# in3watch.net
KiCad netlist of a schematic drawn in EAGLE
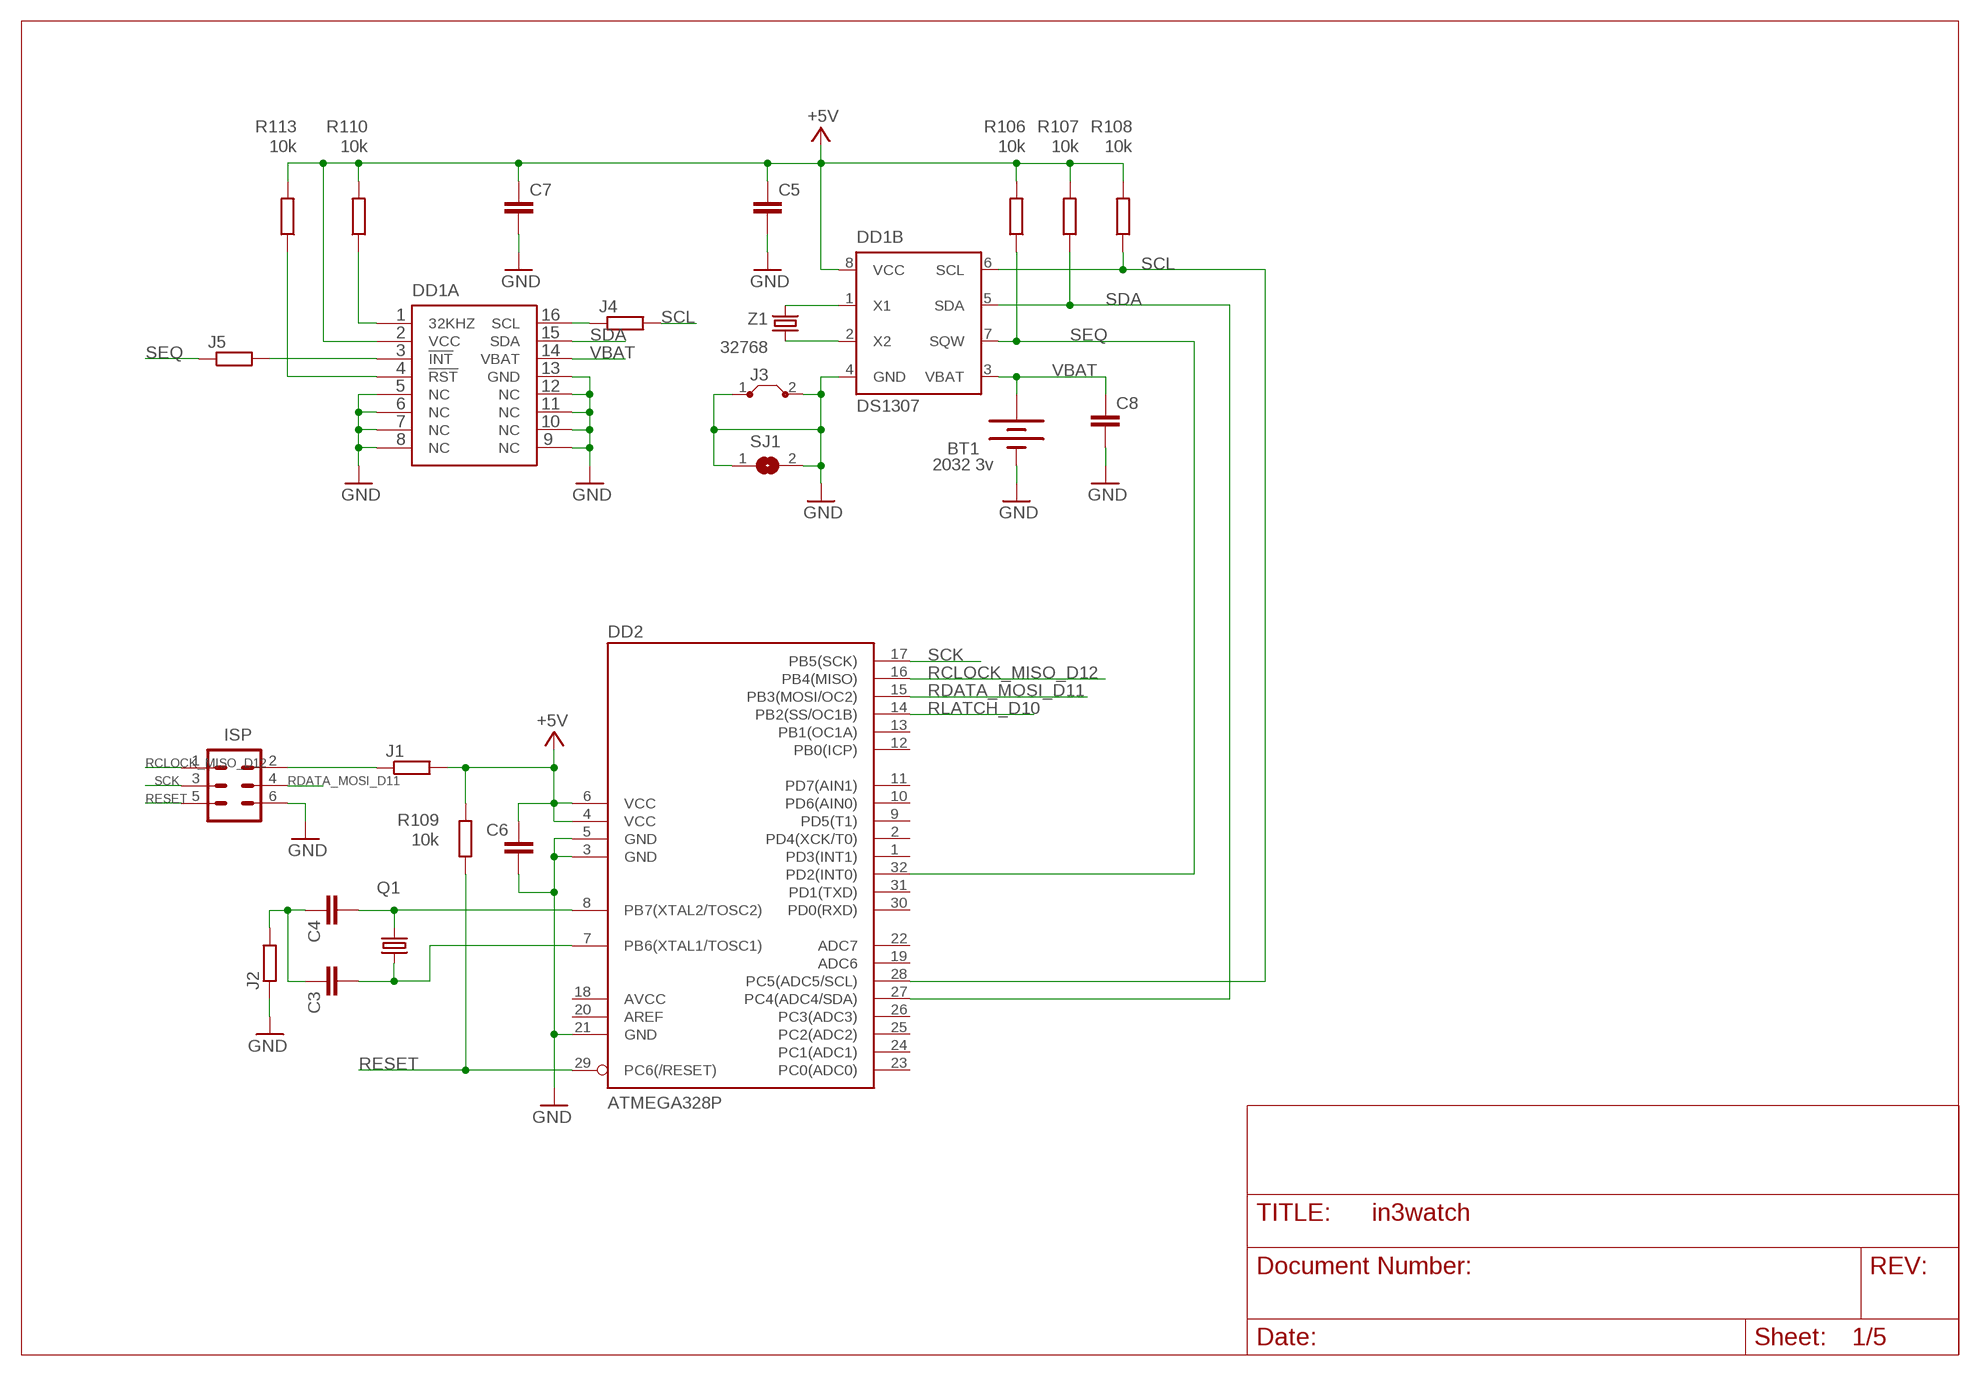
[diagram p0: schematic, sheet 1]
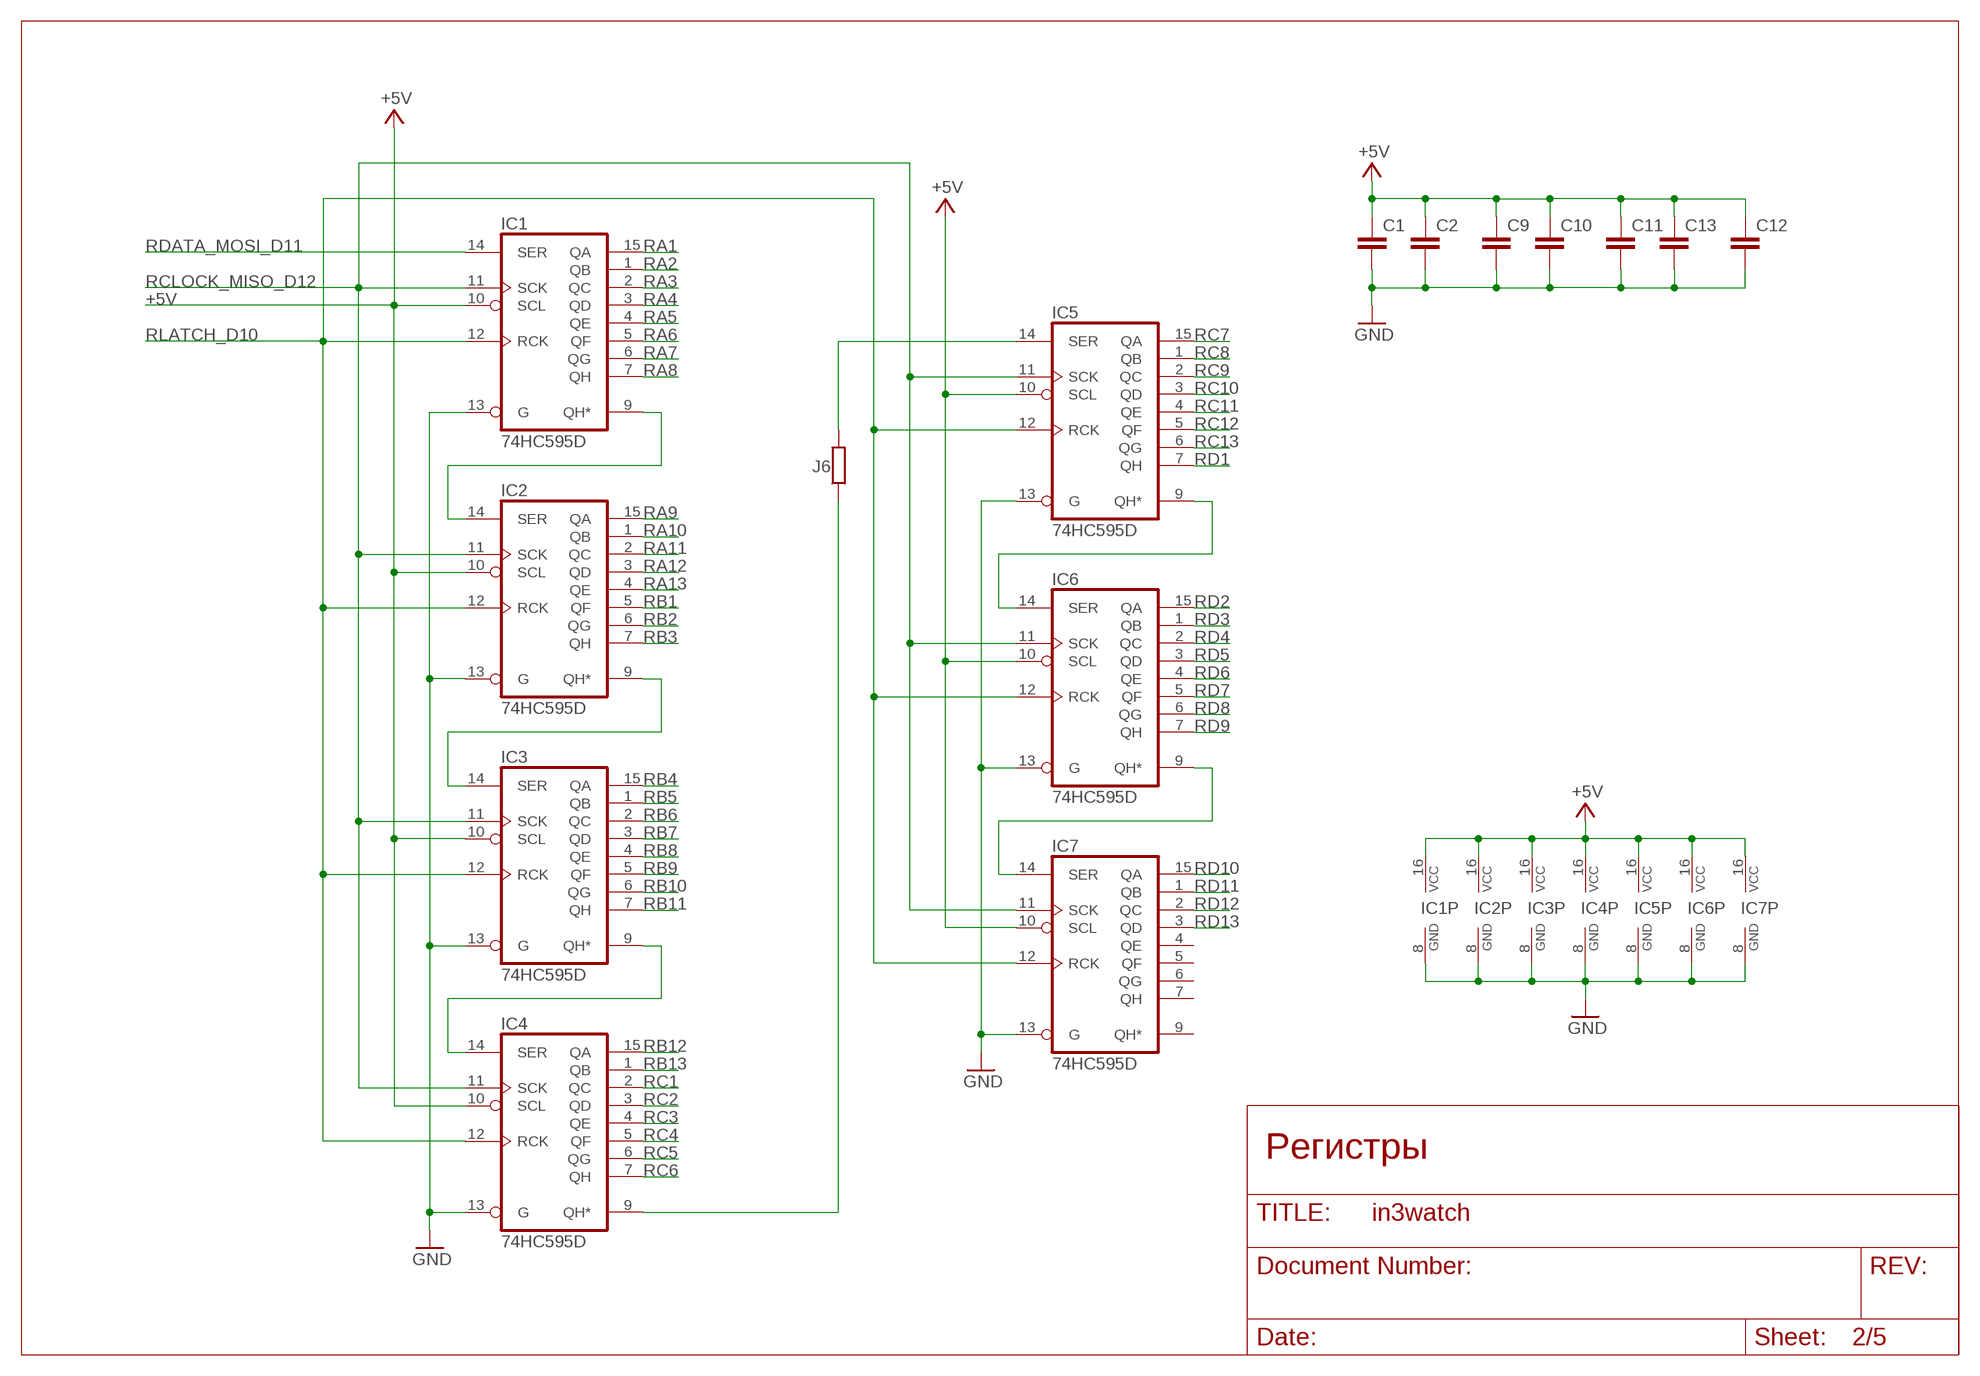
[diagram p1: schematic, sheet 2]
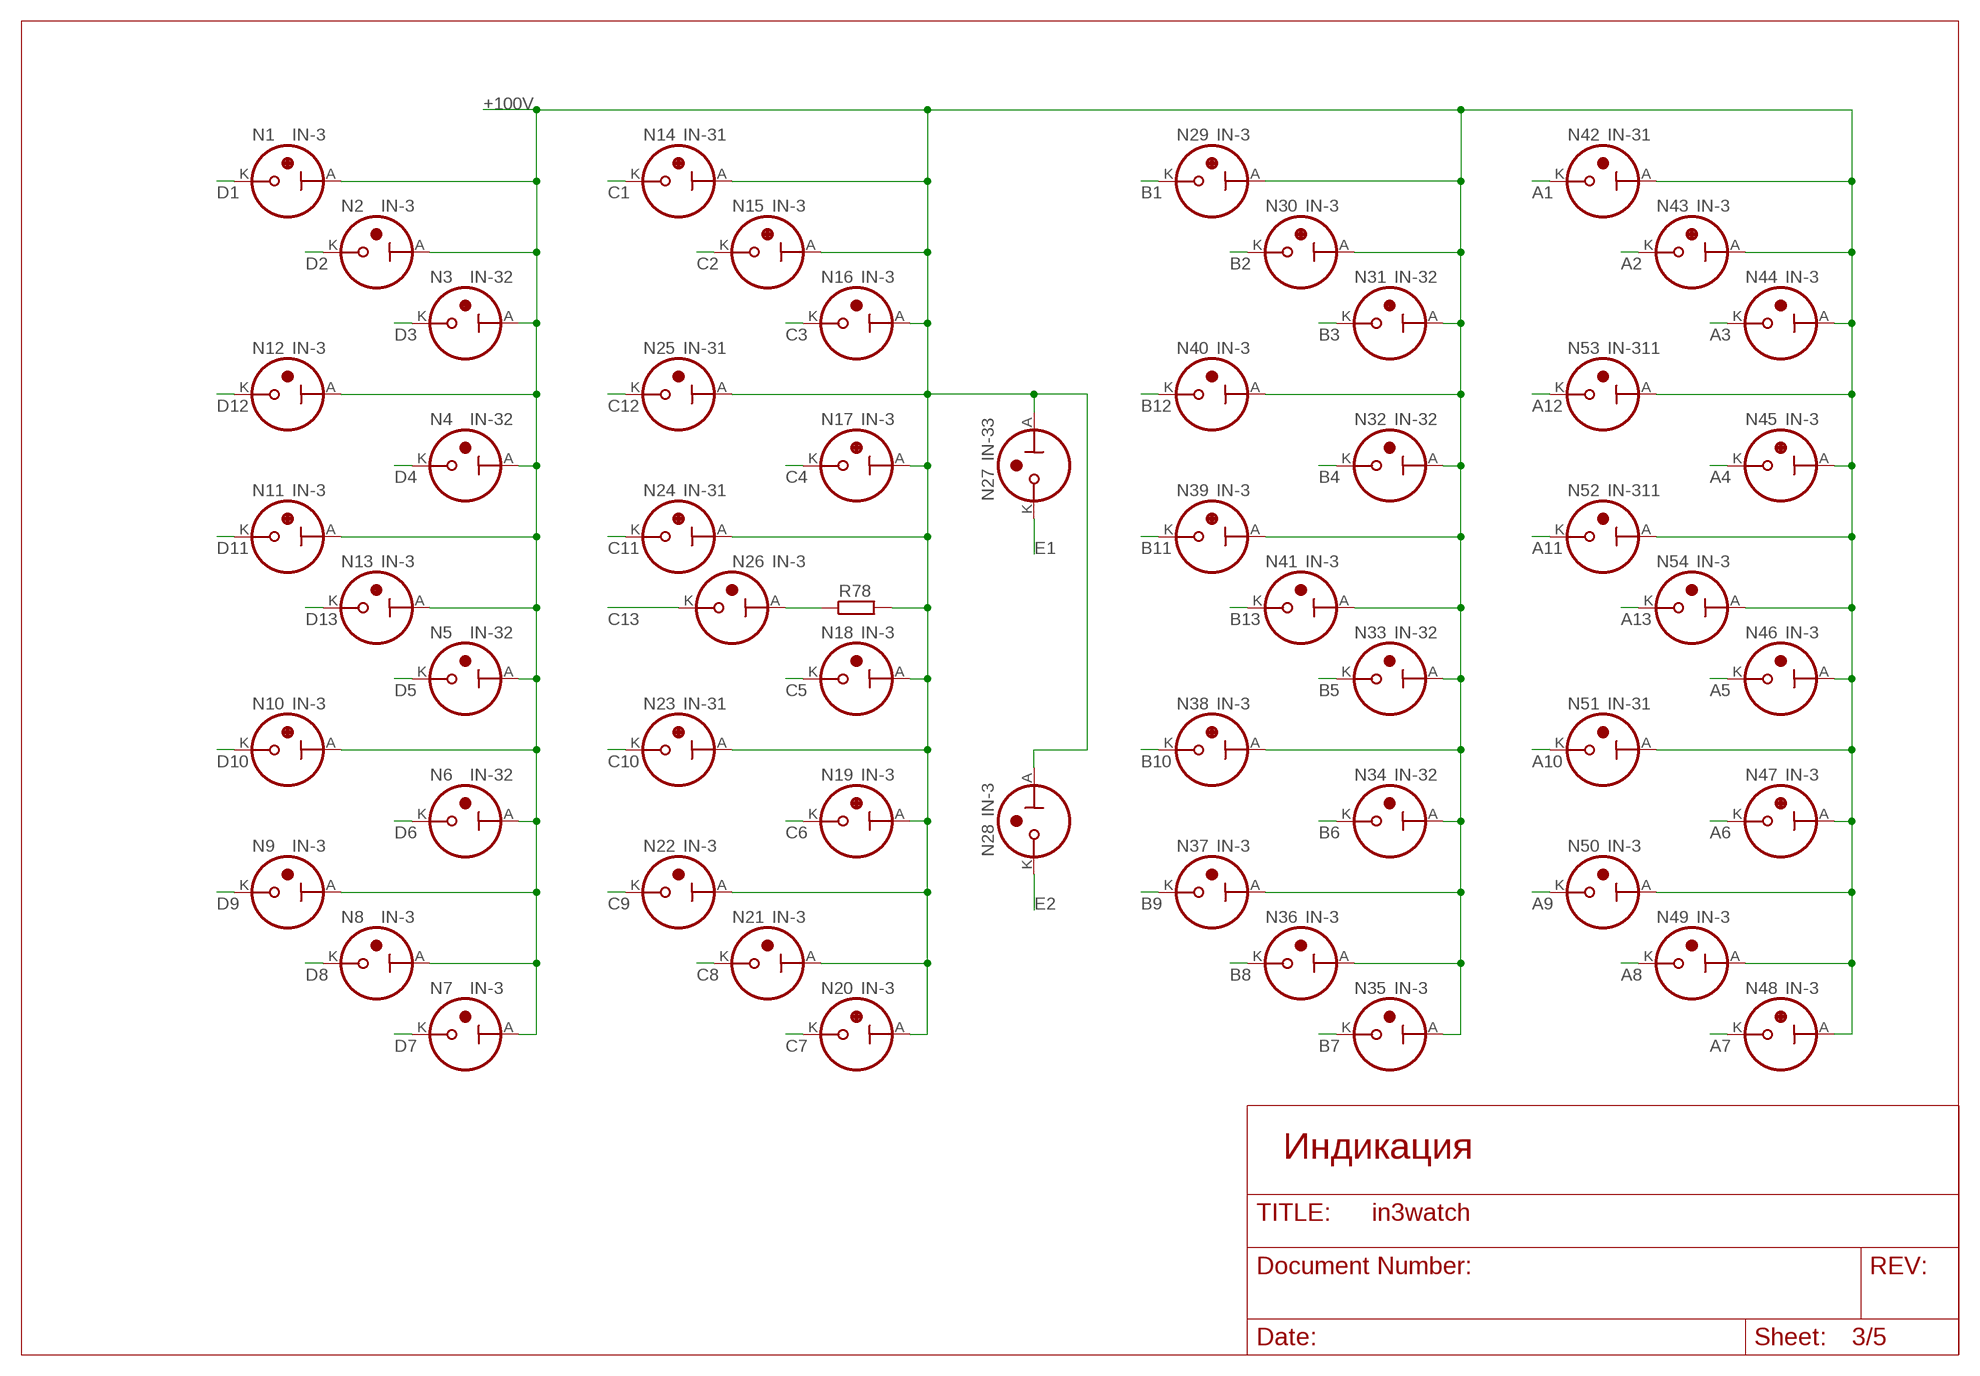
[diagram p2: schematic, sheet 3]
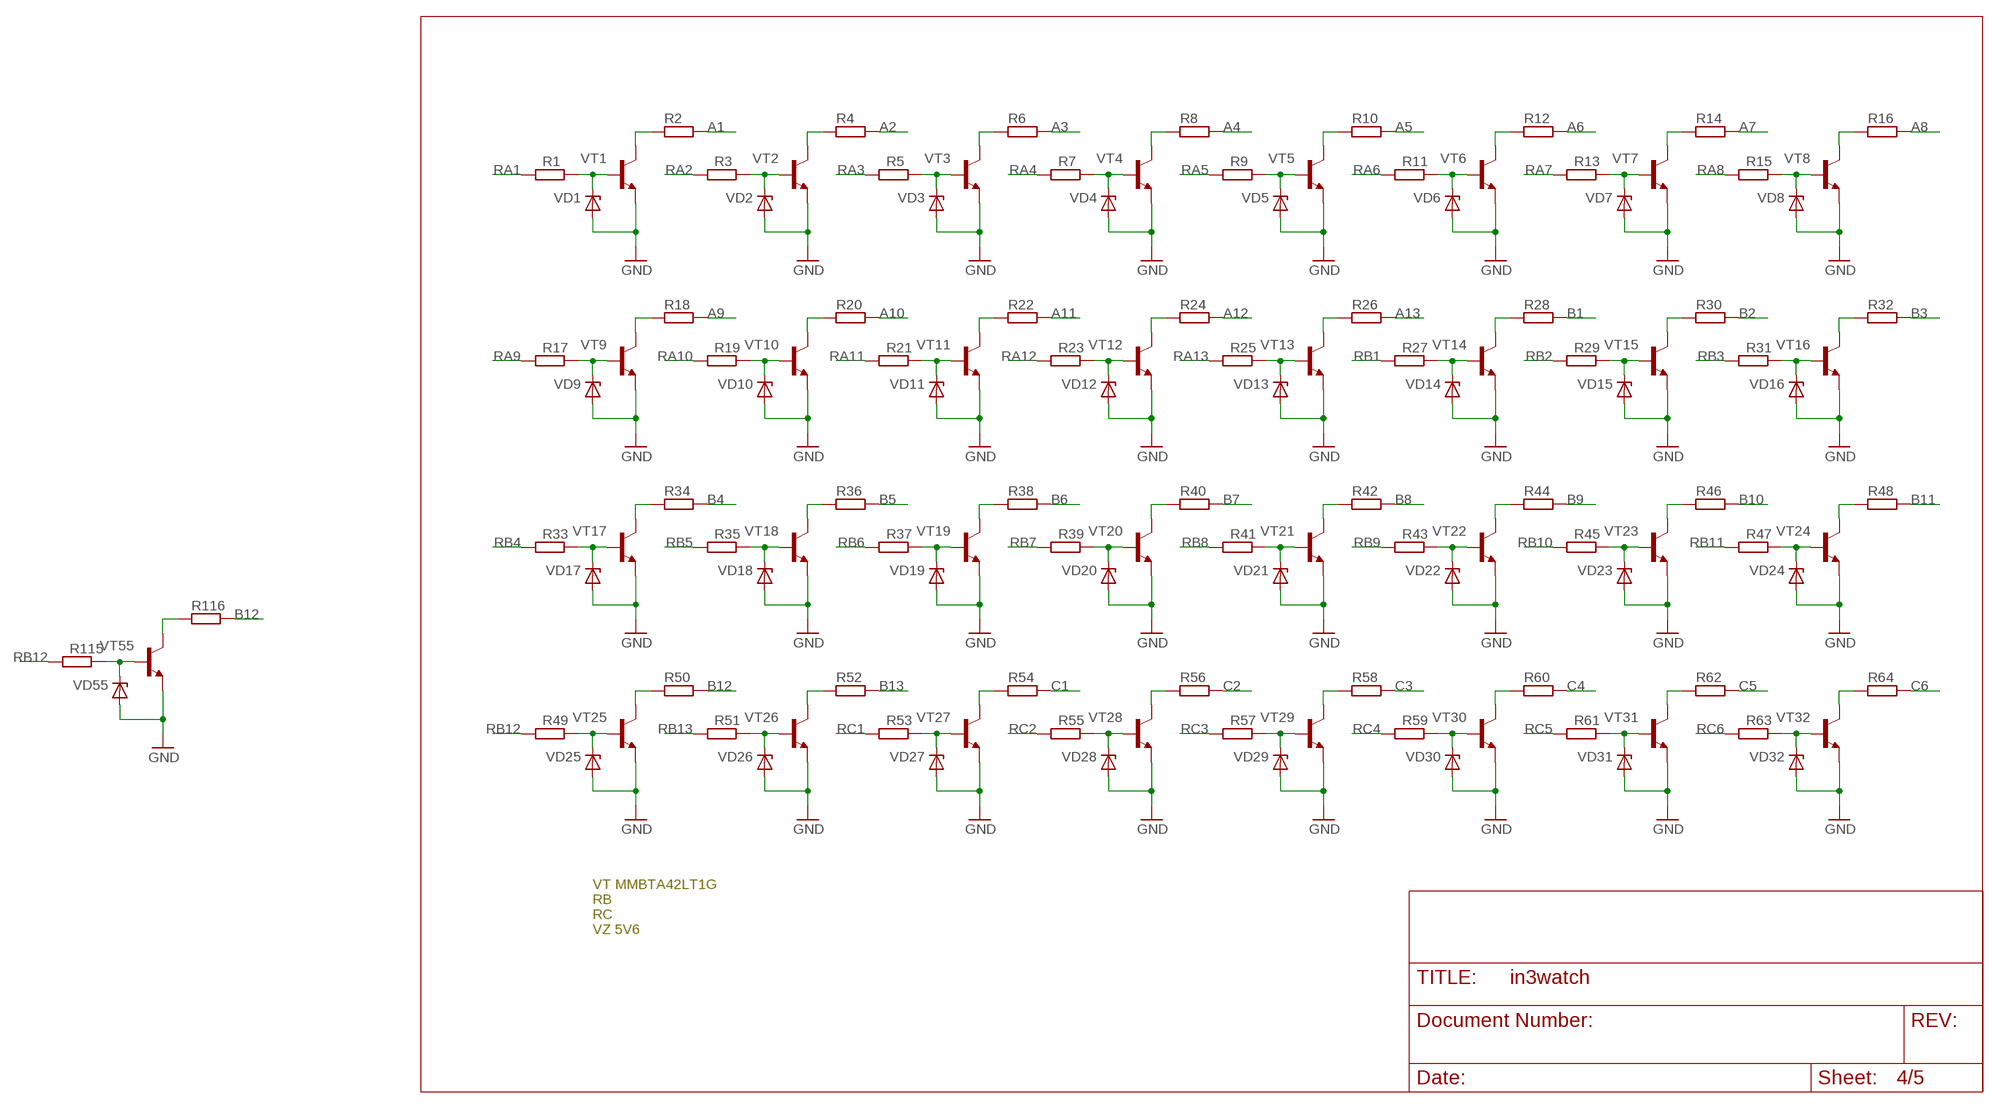
[diagram p3: schematic, sheet 4]
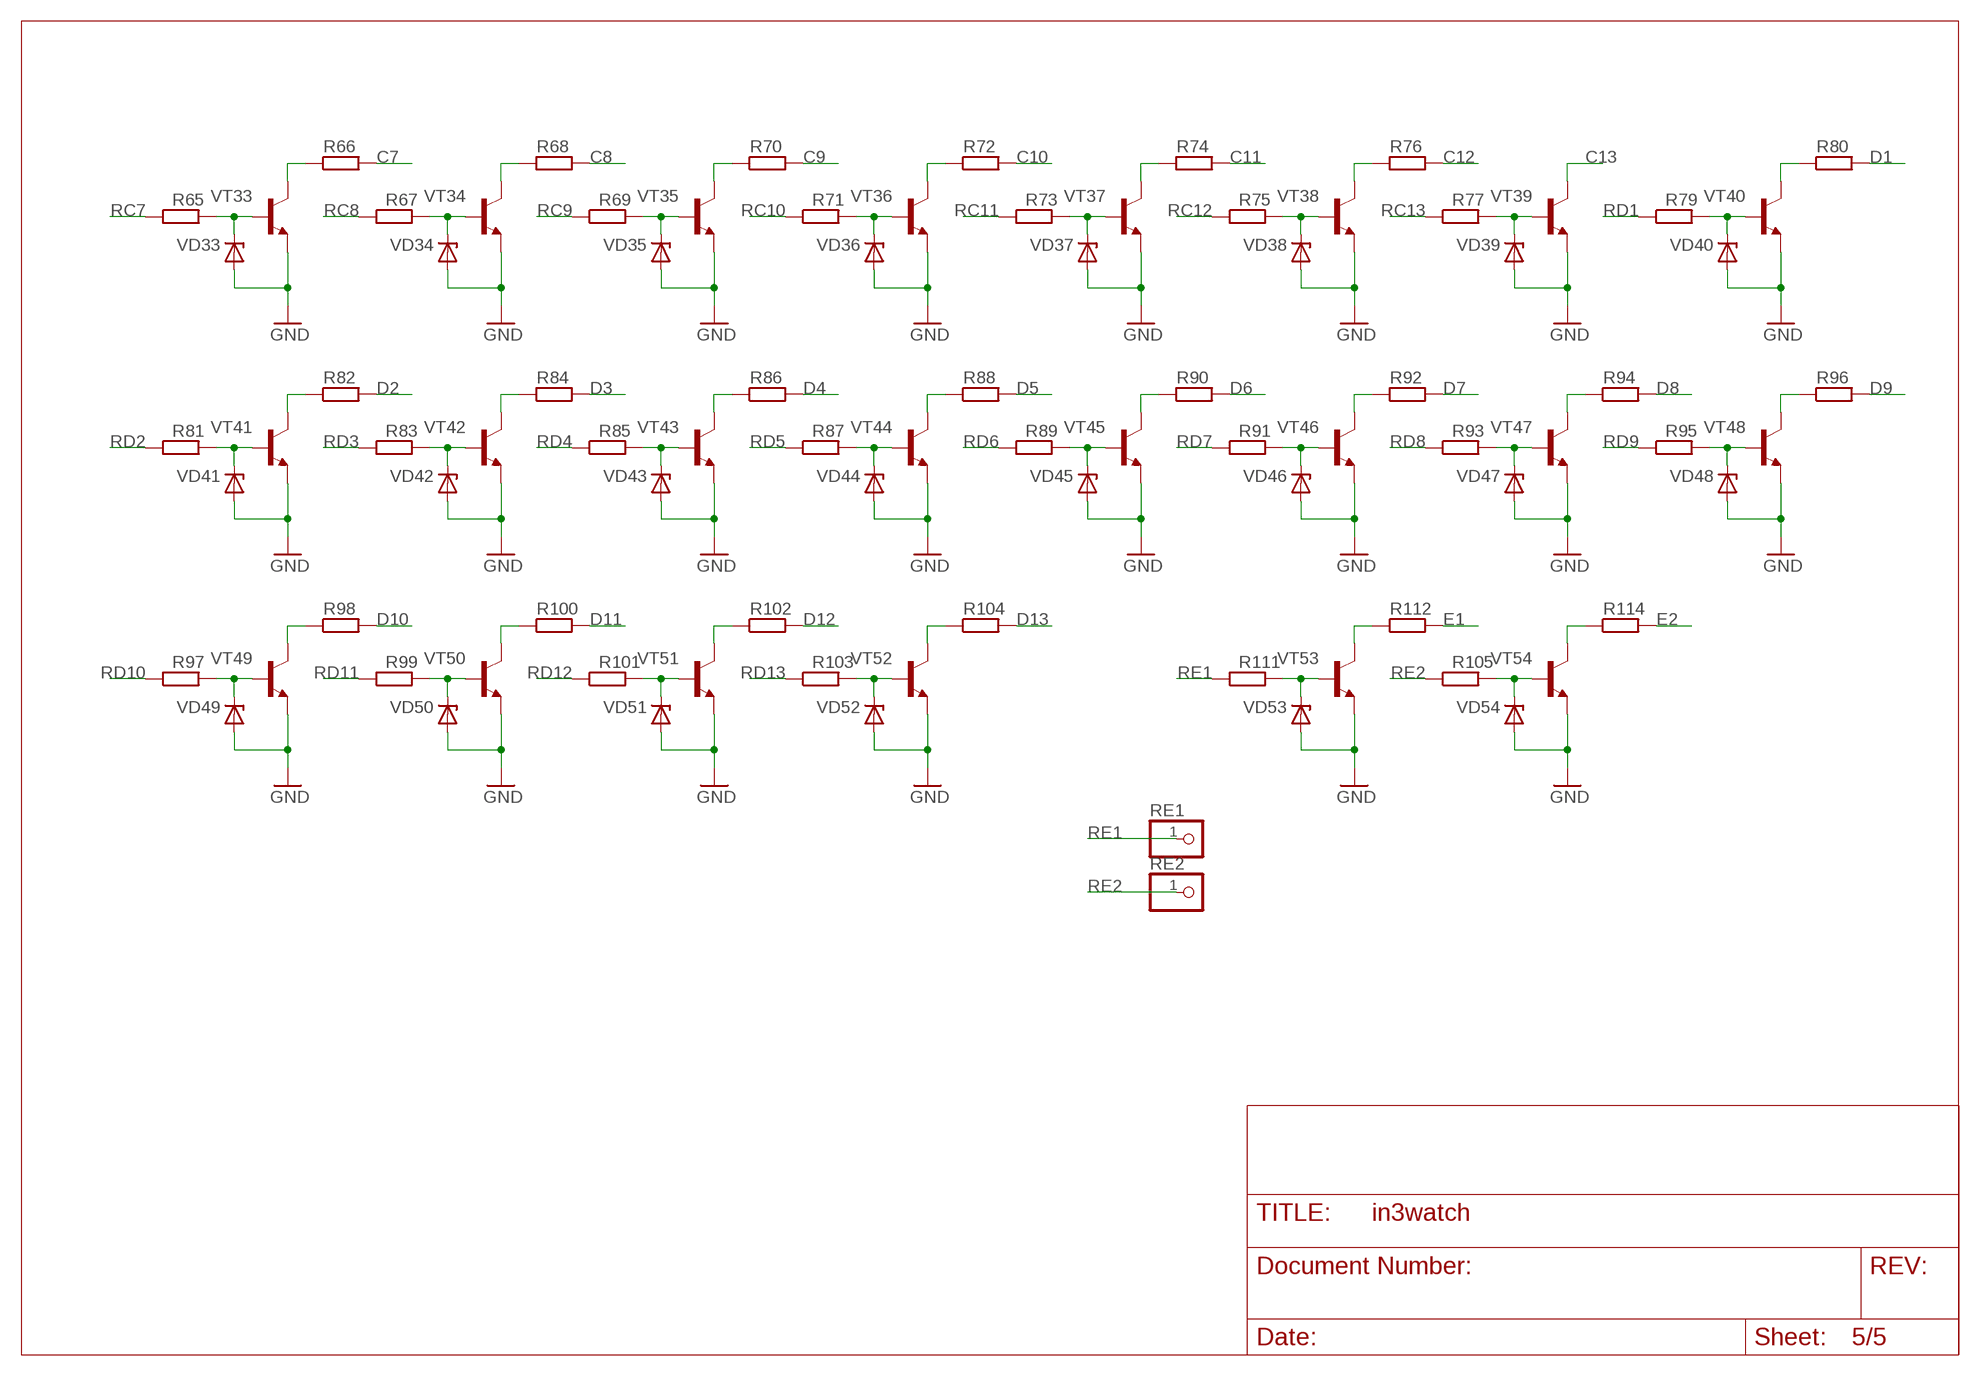
[diagram p4: schematic, sheet 5]

(export (version "E")
  (design (tool "Eeschema 10.0.6"))
  (components
    (comp (ref "N1")
      (value "IN-3")
      (footprint "eagle-import:IN-3")
      (libsource (lib "eagle-import") (part "IN-3"))
    )
    (comp (ref "N2")
      (value "IN-3")
      (footprint "eagle-import:IN-3")
      (libsource (lib "eagle-import") (part "IN-3"))
    )
    (comp (ref "N3")
      (value "IN-32")
      (footprint "eagle-import:IN-3-2")
      (libsource (lib "eagle-import") (part "IN-32"))
    )
    (comp (ref "N4")
      (value "IN-32")
      (footprint "eagle-import:IN-3-2")
      (libsource (lib "eagle-import") (part "IN-32"))
    )
    (comp (ref "N5")
      (value "IN-32")
      (footprint "eagle-import:IN-3-2")
      (libsource (lib "eagle-import") (part "IN-32"))
    )
    (comp (ref "N6")
      (value "IN-32")
      (footprint "eagle-import:IN-3-2")
      (libsource (lib "eagle-import") (part "IN-32"))
    )
    (comp (ref "N7")
      (value "IN-3")
      (footprint "eagle-import:IN-3")
      (libsource (lib "eagle-import") (part "IN-3"))
    )
    (comp (ref "N8")
      (value "IN-3")
      (footprint "eagle-import:IN-3")
      (libsource (lib "eagle-import") (part "IN-3"))
    )
    (comp (ref "N9")
      (value "IN-3")
      (footprint "eagle-import:IN-3")
      (libsource (lib "eagle-import") (part "IN-3"))
    )
    (comp (ref "N10")
      (value "IN-3")
      (footprint "eagle-import:IN-3")
      (libsource (lib "eagle-import") (part "IN-3"))
    )
    (comp (ref "N11")
      (value "IN-3")
      (footprint "eagle-import:IN-3")
      (libsource (lib "eagle-import") (part "IN-3"))
    )
    (comp (ref "N12")
      (value "IN-3")
      (footprint "eagle-import:IN-3")
      (libsource (lib "eagle-import") (part "IN-3"))
    )
    (comp (ref "N13")
      (value "IN-3")
      (footprint "eagle-import:IN-3")
      (libsource (lib "eagle-import") (part "IN-3"))
    )
    (comp (ref "N14")
      (value "IN-31")
      (footprint "eagle-import:IN-3-1")
      (libsource (lib "eagle-import") (part "IN-31"))
    )
    (comp (ref "N15")
      (value "IN-3")
      (footprint "eagle-import:IN-3")
      (libsource (lib "eagle-import") (part "IN-3"))
    )
    (comp (ref "N16")
      (value "IN-3")
      (footprint "eagle-import:IN-3")
      (libsource (lib "eagle-import") (part "IN-3"))
    )
    (comp (ref "N17")
      (value "IN-3")
      (footprint "eagle-import:IN-3")
      (libsource (lib "eagle-import") (part "IN-3"))
    )
    (comp (ref "N18")
      (value "IN-3")
      (footprint "eagle-import:IN-3")
      (libsource (lib "eagle-import") (part "IN-3"))
    )
    (comp (ref "N19")
      (value "IN-3")
      (footprint "eagle-import:IN-3")
      (libsource (lib "eagle-import") (part "IN-3"))
    )
    (comp (ref "N20")
      (value "IN-3")
      (footprint "eagle-import:IN-3")
      (libsource (lib "eagle-import") (part "IN-3"))
    )
    (comp (ref "N21")
      (value "IN-3")
      (footprint "eagle-import:IN-3")
      (libsource (lib "eagle-import") (part "IN-3"))
    )
    (comp (ref "N22")
      (value "IN-3")
      (footprint "eagle-import:IN-3")
      (libsource (lib "eagle-import") (part "IN-3"))
    )
    (comp (ref "N23")
      (value "IN-31")
      (footprint "eagle-import:IN-3-1")
      (libsource (lib "eagle-import") (part "IN-31"))
    )
    (comp (ref "N24")
      (value "IN-31")
      (footprint "eagle-import:IN-3-1")
      (libsource (lib "eagle-import") (part "IN-31"))
    )
    (comp (ref "N25")
      (value "IN-31")
      (footprint "eagle-import:IN-3-1")
      (libsource (lib "eagle-import") (part "IN-31"))
    )
    (comp (ref "N26")
      (value "IN-3")
      (footprint "eagle-import:IN-3")
      (libsource (lib "eagle-import") (part "IN-3"))
    )
    (comp (ref "N27")
      (value "IN-33")
      (footprint "eagle-import:IN-3-3")
      (libsource (lib "eagle-import") (part "IN-33"))
    )
    (comp (ref "N28")
      (value "IN-3")
      (footprint "eagle-import:IN-3")
      (libsource (lib "eagle-import") (part "IN-3"))
    )
    (comp (ref "N29")
      (value "IN-3")
      (footprint "eagle-import:IN-3")
      (libsource (lib "eagle-import") (part "IN-3"))
    )
    (comp (ref "N30")
      (value "IN-3")
      (footprint "eagle-import:IN-3")
      (libsource (lib "eagle-import") (part "IN-3"))
    )
    (comp (ref "N31")
      (value "IN-32")
      (footprint "eagle-import:IN-3-2")
      (libsource (lib "eagle-import") (part "IN-32"))
    )
    (comp (ref "N32")
      (value "IN-32")
      (footprint "eagle-import:IN-3-2")
      (libsource (lib "eagle-import") (part "IN-32"))
    )
    (comp (ref "N33")
      (value "IN-32")
      (footprint "eagle-import:IN-3-2")
      (libsource (lib "eagle-import") (part "IN-32"))
    )
    (comp (ref "N34")
      (value "IN-32")
      (footprint "eagle-import:IN-3-2")
      (libsource (lib "eagle-import") (part "IN-32"))
    )
    (comp (ref "N35")
      (value "IN-3")
      (footprint "eagle-import:IN-3")
      (libsource (lib "eagle-import") (part "IN-3"))
    )
    (comp (ref "N36")
      (value "IN-3")
      (footprint "eagle-import:IN-3")
      (libsource (lib "eagle-import") (part "IN-3"))
    )
    (comp (ref "N37")
      (value "IN-3")
      (footprint "eagle-import:IN-3")
      (libsource (lib "eagle-import") (part "IN-3"))
    )
    (comp (ref "N38")
      (value "IN-3")
      (footprint "eagle-import:IN-3")
      (libsource (lib "eagle-import") (part "IN-3"))
    )
    (comp (ref "N39")
      (value "IN-3")
      (footprint "eagle-import:IN-3")
      (libsource (lib "eagle-import") (part "IN-3"))
    )
    (comp (ref "N40")
      (value "IN-3")
      (footprint "eagle-import:IN-3")
      (libsource (lib "eagle-import") (part "IN-3"))
    )
    (comp (ref "N41")
      (value "IN-3")
      (footprint "eagle-import:IN-3")
      (libsource (lib "eagle-import") (part "IN-3"))
    )
    (comp (ref "N42")
      (value "IN-31")
      (footprint "eagle-import:IN-3-1")
      (libsource (lib "eagle-import") (part "IN-31"))
    )
    (comp (ref "N43")
      (value "IN-3")
      (footprint "eagle-import:IN-3")
      (libsource (lib "eagle-import") (part "IN-3"))
    )
    (comp (ref "N44")
      (value "IN-3")
      (footprint "eagle-import:IN-3")
      (libsource (lib "eagle-import") (part "IN-3"))
    )
    (comp (ref "N45")
      (value "IN-3")
      (footprint "eagle-import:IN-3")
      (libsource (lib "eagle-import") (part "IN-3"))
    )
    (comp (ref "N46")
      (value "IN-3")
      (footprint "eagle-import:IN-3")
      (libsource (lib "eagle-import") (part "IN-3"))
    )
    (comp (ref "N47")
      (value "IN-3")
      (footprint "eagle-import:IN-3")
      (libsource (lib "eagle-import") (part "IN-3"))
    )
    (comp (ref "N48")
      (value "IN-3")
      (footprint "eagle-import:IN-3")
      (libsource (lib "eagle-import") (part "IN-3"))
    )
    (comp (ref "N49")
      (value "IN-3")
      (footprint "eagle-import:IN-3")
      (libsource (lib "eagle-import") (part "IN-3"))
    )
    (comp (ref "N50")
      (value "IN-3")
      (footprint "eagle-import:IN-3")
      (libsource (lib "eagle-import") (part "IN-3"))
    )
    (comp (ref "N51")
      (value "IN-31")
      (footprint "eagle-import:IN-3-1")
      (libsource (lib "eagle-import") (part "IN-31"))
    )
    (comp (ref "N52")
      (value "IN-311")
      (footprint "eagle-import:IN-3-11")
      (libsource (lib "eagle-import") (part "IN-311"))
    )
    (comp (ref "N53")
      (value "IN-311")
      (footprint "eagle-import:IN-3-11")
      (libsource (lib "eagle-import") (part "IN-311"))
    )
    (comp (ref "N54")
      (value "IN-3")
      (footprint "eagle-import:IN-3")
      (libsource (lib "eagle-import") (part "IN-3"))
    )
    (comp (ref "R78")
      (value "R-EU_0207/15")
      (footprint "eagle-import:0207_15")
      (libsource (lib "eagle-import") (part "R-EU_0207/15"))
    )
    (comp (ref "R1")
      (value "R-EU_R0805")
      (footprint "eagle-import:R0805")
      (libsource (lib "eagle-import") (part "R-EU_R0805"))
    )
    (comp (ref "R2")
      (value "R-EU_0207/12")
      (footprint "eagle-import:0207_12")
      (libsource (lib "eagle-import") (part "R-EU_0207/12"))
    )
    (comp (ref "R3")
      (value "R-EU_R0805")
      (footprint "eagle-import:R0805")
      (libsource (lib "eagle-import") (part "R-EU_R0805"))
    )
    (comp (ref "R4")
      (value "R-EU_0207/12")
      (footprint "eagle-import:0207_12")
      (libsource (lib "eagle-import") (part "R-EU_0207/12"))
    )
    (comp (ref "R5")
      (value "R-EU_R0805")
      (footprint "eagle-import:R0805")
      (libsource (lib "eagle-import") (part "R-EU_R0805"))
    )
    (comp (ref "R6")
      (value "R-EU_0207/12")
      (footprint "eagle-import:0207_12")
      (libsource (lib "eagle-import") (part "R-EU_0207/12"))
    )
    (comp (ref "R7")
      (value "R-EU_R0805")
      (footprint "eagle-import:R0805")
      (libsource (lib "eagle-import") (part "R-EU_R0805"))
    )
    (comp (ref "R8")
      (value "R-EU_0207/12")
      (footprint "eagle-import:0207_12")
      (libsource (lib "eagle-import") (part "R-EU_0207/12"))
    )
    (comp (ref "R9")
      (value "R-EU_R0805")
      (footprint "eagle-import:R0805")
      (libsource (lib "eagle-import") (part "R-EU_R0805"))
    )
    (comp (ref "R10")
      (value "R-EU_0207/12")
      (footprint "eagle-import:0207_12")
      (libsource (lib "eagle-import") (part "R-EU_0207/12"))
    )
    (comp (ref "R11")
      (value "R-EU_R0805")
      (footprint "eagle-import:R0805")
      (libsource (lib "eagle-import") (part "R-EU_R0805"))
    )
    (comp (ref "R12")
      (value "R-EU_0207/12")
      (footprint "eagle-import:0207_12")
      (libsource (lib "eagle-import") (part "R-EU_0207/12"))
    )
    (comp (ref "R13")
      (value "R-EU_R0805")
      (footprint "eagle-import:R0805")
      (libsource (lib "eagle-import") (part "R-EU_R0805"))
    )
    (comp (ref "R14")
      (value "R-EU_0207/12")
      (footprint "eagle-import:0207_12")
      (libsource (lib "eagle-import") (part "R-EU_0207/12"))
    )
    (comp (ref "R15")
      (value "R-EU_R0805")
      (footprint "eagle-import:R0805")
      (libsource (lib "eagle-import") (part "R-EU_R0805"))
    )
    (comp (ref "R16")
      (value "R-EU_0207/12")
      (footprint "eagle-import:0207_12")
      (libsource (lib "eagle-import") (part "R-EU_0207/12"))
    )
    (comp (ref "R17")
      (value "R-EU_R0805")
      (footprint "eagle-import:R0805")
      (libsource (lib "eagle-import") (part "R-EU_R0805"))
    )
    (comp (ref "R18")
      (value "R-EU_0207/12")
      (footprint "eagle-import:0207_12")
      (libsource (lib "eagle-import") (part "R-EU_0207/12"))
    )
    (comp (ref "R19")
      (value "R-EU_R1206W")
      (footprint "eagle-import:R1206W")
      (libsource (lib "eagle-import") (part "R-EU_R1206W"))
    )
    (comp (ref "R20")
      (value "R-EU_0207/12")
      (footprint "eagle-import:0207_12")
      (libsource (lib "eagle-import") (part "R-EU_0207/12"))
    )
    (comp (ref "R21")
      (value "R-EU_R0805")
      (footprint "eagle-import:R0805")
      (libsource (lib "eagle-import") (part "R-EU_R0805"))
    )
    (comp (ref "R22")
      (value "R-EU_0207/12")
      (footprint "eagle-import:0207_12")
      (libsource (lib "eagle-import") (part "R-EU_0207/12"))
    )
    (comp (ref "R23")
      (value "R-EU_R0805")
      (footprint "eagle-import:R0805")
      (libsource (lib "eagle-import") (part "R-EU_R0805"))
    )
    (comp (ref "R24")
      (value "R-EU_0207/12")
      (footprint "eagle-import:0207_12")
      (libsource (lib "eagle-import") (part "R-EU_0207/12"))
    )
    (comp (ref "R25")
      (value "R-EU_R0805")
      (footprint "eagle-import:R0805")
      (libsource (lib "eagle-import") (part "R-EU_R0805"))
    )
    (comp (ref "R26")
      (value "R-EU_0207/12")
      (footprint "eagle-import:0207_12")
      (libsource (lib "eagle-import") (part "R-EU_0207/12"))
    )
    (comp (ref "R27")
      (value "R-EU_R0805")
      (footprint "eagle-import:R0805")
      (libsource (lib "eagle-import") (part "R-EU_R0805"))
    )
    (comp (ref "R28")
      (value "R-EU_0207/12")
      (footprint "eagle-import:0207_12")
      (libsource (lib "eagle-import") (part "R-EU_0207/12"))
    )
    (comp (ref "R29")
      (value "R-EU_R0805")
      (footprint "eagle-import:R0805")
      (libsource (lib "eagle-import") (part "R-EU_R0805"))
    )
    (comp (ref "R30")
      (value "R-EU_0207/12")
      (footprint "eagle-import:0207_12")
      (libsource (lib "eagle-import") (part "R-EU_0207/12"))
    )
    (comp (ref "R31")
      (value "R-EU_R0805")
      (footprint "eagle-import:R0805")
      (libsource (lib "eagle-import") (part "R-EU_R0805"))
    )
    (comp (ref "R32")
      (value "R-EU_0207/12")
      (footprint "eagle-import:0207_12")
      (libsource (lib "eagle-import") (part "R-EU_0207/12"))
    )
    (comp (ref "R33")
      (value "R-EU_R0805")
      (footprint "eagle-import:R0805")
      (libsource (lib "eagle-import") (part "R-EU_R0805"))
    )
    (comp (ref "R34")
      (value "R-EU_0207/12")
      (footprint "eagle-import:0207_12")
      (libsource (lib "eagle-import") (part "R-EU_0207/12"))
    )
    (comp (ref "R35")
      (value "R-EU_M1206")
      (footprint "eagle-import:M1206")
      (libsource (lib "eagle-import") (part "R-EU_M1206"))
    )
    (comp (ref "R36")
      (value "R-EU_0207/12")
      (footprint "eagle-import:0207_12")
      (libsource (lib "eagle-import") (part "R-EU_0207/12"))
    )
    (comp (ref "R37")
      (value "R-EU_R0805")
      (footprint "eagle-import:R0805")
      (libsource (lib "eagle-import") (part "R-EU_R0805"))
    )
    (comp (ref "R38")
      (value "R-EU_0207/12")
      (footprint "eagle-import:0207_12")
      (libsource (lib "eagle-import") (part "R-EU_0207/12"))
    )
    (comp (ref "R39")
      (value "R-EU_R0805")
      (footprint "eagle-import:R0805")
      (libsource (lib "eagle-import") (part "R-EU_R0805"))
    )
    (comp (ref "R40")
      (value "R-EU_0207/12")
      (footprint "eagle-import:0207_12")
      (libsource (lib "eagle-import") (part "R-EU_0207/12"))
    )
    (comp (ref "R41")
      (value "R-EU_R1206W")
      (footprint "eagle-import:R1206W")
      (libsource (lib "eagle-import") (part "R-EU_R1206W"))
    )
    (comp (ref "R42")
      (value "R-EU_0207/12")
      (footprint "eagle-import:0207_12")
      (libsource (lib "eagle-import") (part "R-EU_0207/12"))
    )
    (comp (ref "R43")
      (value "R-EU_R1206W")
      (footprint "eagle-import:R1206W")
      (libsource (lib "eagle-import") (part "R-EU_R1206W"))
    )
    (comp (ref "R44")
      (value "R-EU_0207/12")
      (footprint "eagle-import:0207_12")
      (libsource (lib "eagle-import") (part "R-EU_0207/12"))
    )
    (comp (ref "R45")
      (value "R-EU_R1206W")
      (footprint "eagle-import:R1206W")
      (libsource (lib "eagle-import") (part "R-EU_R1206W"))
    )
    (comp (ref "R46")
      (value "R-EU_0207/12")
      (footprint "eagle-import:0207_12")
      (libsource (lib "eagle-import") (part "R-EU_0207/12"))
    )
    (comp (ref "R47")
      (value "R-EU_R0805")
      (footprint "eagle-import:R0805")
      (libsource (lib "eagle-import") (part "R-EU_R0805"))
    )
    (comp (ref "R48")
      (value "R-EU_0207/10")
      (footprint "eagle-import:0207_10")
      (libsource (lib "eagle-import") (part "R-EU_0207/10"))
    )
    (comp (ref "R49")
      (value "R-EU_R0805")
      (footprint "eagle-import:R0805")
      (libsource (lib "eagle-import") (part "R-EU_R0805"))
    )
    (comp (ref "R50")
      (value "R-EU_0207/12")
      (footprint "eagle-import:0207_12")
      (libsource (lib "eagle-import") (part "R-EU_0207/12"))
    )
    (comp (ref "R51")
      (value "R-EU_R0805")
      (footprint "eagle-import:R0805")
      (libsource (lib "eagle-import") (part "R-EU_R0805"))
    )
    (comp (ref "R52")
      (value "R-EU_0207/12")
      (footprint "eagle-import:0207_12")
      (libsource (lib "eagle-import") (part "R-EU_0207/12"))
    )
    (comp (ref "R53")
      (value "R-EU_R0805")
      (footprint "eagle-import:R0805")
      (libsource (lib "eagle-import") (part "R-EU_R0805"))
    )
    (comp (ref "R54")
      (value "R-EU_0207/12")
      (footprint "eagle-import:0207_12")
      (libsource (lib "eagle-import") (part "R-EU_0207/12"))
    )
    (comp (ref "R55")
      (value "R-EU_R0805")
      (footprint "eagle-import:R0805")
      (libsource (lib "eagle-import") (part "R-EU_R0805"))
    )
    (comp (ref "R56")
      (value "R-EU_0207/10")
      (footprint "eagle-import:0207_10")
      (libsource (lib "eagle-import") (part "R-EU_0207/10"))
    )
    (comp (ref "R57")
      (value "R-EU_R0805")
      (footprint "eagle-import:R0805")
      (libsource (lib "eagle-import") (part "R-EU_R0805"))
    )
    (comp (ref "R58")
      (value "R-EU_0207/12")
      (footprint "eagle-import:0207_12")
      (libsource (lib "eagle-import") (part "R-EU_0207/12"))
    )
    (comp (ref "R59")
      (value "R-EU_R0805")
      (footprint "eagle-import:R0805")
      (libsource (lib "eagle-import") (part "R-EU_R0805"))
    )
    (comp (ref "R60")
      (value "R-EU_0207/12")
      (footprint "eagle-import:0207_12")
      (libsource (lib "eagle-import") (part "R-EU_0207/12"))
    )
    (comp (ref "R61")
      (value "R-EU_R0805")
      (footprint "eagle-import:R0805")
      (libsource (lib "eagle-import") (part "R-EU_R0805"))
    )
    (comp (ref "R62")
      (value "R-EU_0207/12")
      (footprint "eagle-import:0207_12")
      (libsource (lib "eagle-import") (part "R-EU_0207/12"))
    )
    (comp (ref "R63")
      (value "R-EU_R0805")
      (footprint "eagle-import:R0805")
      (libsource (lib "eagle-import") (part "R-EU_R0805"))
    )
    (comp (ref "R64")
      (value "R-EU_0207/12")
      (footprint "eagle-import:0207_12")
      (libsource (lib "eagle-import") (part "R-EU_0207/12"))
    )
    (comp (ref "R115")
      (value "R-EU_R0603")
      (footprint "eagle-import:R0603")
      (libsource (lib "eagle-import") (part "R-EU_R0603"))
    )
    (comp (ref "R116")
      (value "R-EU_R0603")
      (footprint "eagle-import:R0603")
      (libsource (lib "eagle-import") (part "R-EU_R0603"))
    )
    (comp (ref "VD1")
      (value "ZENER-DIODESOD80C")
      (footprint "eagle-import:SOD80C")
      (libsource (lib "eagle-import") (part "ZENER-DIODESOD80C"))
    )
    (comp (ref "VD2")
      (value "ZENER-DIODESOD80C")
      (footprint "eagle-import:SOD80C")
      (libsource (lib "eagle-import") (part "ZENER-DIODESOD80C"))
    )
    (comp (ref "VD3")
      (value "ZENER-DIODESOD80C")
      (footprint "eagle-import:SOD80C")
      (libsource (lib "eagle-import") (part "ZENER-DIODESOD80C"))
    )
    (comp (ref "VD4")
      (value "ZENER-DIODESOD80C")
      (footprint "eagle-import:SOD80C")
      (libsource (lib "eagle-import") (part "ZENER-DIODESOD80C"))
    )
    (comp (ref "VD5")
      (value "ZENER-DIODESOD80C")
      (footprint "eagle-import:SOD80C")
      (libsource (lib "eagle-import") (part "ZENER-DIODESOD80C"))
    )
    (comp (ref "VD6")
      (value "ZENER-DIODESOD80C")
      (footprint "eagle-import:SOD80C")
      (libsource (lib "eagle-import") (part "ZENER-DIODESOD80C"))
    )
    (comp (ref "VD7")
      (value "ZENER-DIODESOD80C")
      (footprint "eagle-import:SOD80C")
      (libsource (lib "eagle-import") (part "ZENER-DIODESOD80C"))
    )
    (comp (ref "VD8")
      (value "ZENER-DIODESOD80C")
      (footprint "eagle-import:SOD80C")
      (libsource (lib "eagle-import") (part "ZENER-DIODESOD80C"))
    )
    (comp (ref "VD9")
      (value "ZENER-DIODESOD80C")
      (footprint "eagle-import:SOD80C")
      (libsource (lib "eagle-import") (part "ZENER-DIODESOD80C"))
    )
    (comp (ref "VD10")
      (value "ZENER-DIODESOD80C")
      (footprint "eagle-import:SOD80C")
      (libsource (lib "eagle-import") (part "ZENER-DIODESOD80C"))
    )
    (comp (ref "VD11")
      (value "ZENER-DIODESOD80C")
      (footprint "eagle-import:SOD80C")
      (libsource (lib "eagle-import") (part "ZENER-DIODESOD80C"))
    )
    (comp (ref "VD12")
      (value "ZENER-DIODESOD80C")
      (footprint "eagle-import:SOD80C")
      (libsource (lib "eagle-import") (part "ZENER-DIODESOD80C"))
    )
    (comp (ref "VD13")
      (value "ZENER-DIODESOD80C")
      (footprint "eagle-import:SOD80C")
      (libsource (lib "eagle-import") (part "ZENER-DIODESOD80C"))
    )
    (comp (ref "VD14")
      (value "ZENER-DIODESOD80C")
      (footprint "eagle-import:SOD80C")
      (libsource (lib "eagle-import") (part "ZENER-DIODESOD80C"))
    )
    (comp (ref "VD15")
      (value "ZENER-DIODESOD80C")
      (footprint "eagle-import:SOD80C")
      (libsource (lib "eagle-import") (part "ZENER-DIODESOD80C"))
    )
    (comp (ref "VD16")
      (value "ZENER-DIODESOD80C")
      (footprint "eagle-import:SOD80C")
      (libsource (lib "eagle-import") (part "ZENER-DIODESOD80C"))
    )
    (comp (ref "VD17")
      (value "ZENER-DIODESOD80C")
      (footprint "eagle-import:SOD80C")
      (libsource (lib "eagle-import") (part "ZENER-DIODESOD80C"))
    )
    (comp (ref "VD18")
      (value "ZENER-DIODESOD80C")
      (footprint "eagle-import:SOD80C")
      (libsource (lib "eagle-import") (part "ZENER-DIODESOD80C"))
    )
    (comp (ref "VD19")
      (value "ZENER-DIODESOD80C")
      (footprint "eagle-import:SOD80C")
      (libsource (lib "eagle-import") (part "ZENER-DIODESOD80C"))
    )
    (comp (ref "VD20")
      (value "ZENER-DIODESOD80C")
      (footprint "eagle-import:SOD80C")
      (libsource (lib "eagle-import") (part "ZENER-DIODESOD80C"))
    )
    (comp (ref "VD21")
      (value "ZENER-DIODESOD80C")
      (footprint "eagle-import:SOD80C")
      (libsource (lib "eagle-import") (part "ZENER-DIODESOD80C"))
    )
    (comp (ref "VD22")
      (value "ZENER-DIODESOD80C")
      (footprint "eagle-import:SOD80C")
      (libsource (lib "eagle-import") (part "ZENER-DIODESOD80C"))
    )
    (comp (ref "VD23")
      (value "ZENER-DIODESOD80C")
      (footprint "eagle-import:SOD80C")
      (libsource (lib "eagle-import") (part "ZENER-DIODESOD80C"))
    )
    (comp (ref "VD24")
      (value "ZENER-DIODESOD80C")
      (footprint "eagle-import:SOD80C")
      (libsource (lib "eagle-import") (part "ZENER-DIODESOD80C"))
    )
    (comp (ref "VD25")
      (value "ZENER-DIODESOD80C")
      (footprint "eagle-import:SOD80C")
      (libsource (lib "eagle-import") (part "ZENER-DIODESOD80C"))
    )
    (comp (ref "VD26")
      (value "ZENER-DIODESOD80C")
      (footprint "eagle-import:SOD80C")
      (libsource (lib "eagle-import") (part "ZENER-DIODESOD80C"))
    )
    (comp (ref "VD27")
      (value "ZENER-DIODESOD80C")
      (footprint "eagle-import:SOD80C")
      (libsource (lib "eagle-import") (part "ZENER-DIODESOD80C"))
    )
    (comp (ref "VD28")
      (value "ZENER-DIODESOD80C")
      (footprint "eagle-import:SOD80C")
      (libsource (lib "eagle-import") (part "ZENER-DIODESOD80C"))
    )
    (comp (ref "VD29")
      (value "ZENER-DIODESOD80C")
      (footprint "eagle-import:SOD80C")
      (libsource (lib "eagle-import") (part "ZENER-DIODESOD80C"))
    )
    (comp (ref "VD30")
      (value "ZENER-DIODESOD80C")
      (footprint "eagle-import:SOD80C")
      (libsource (lib "eagle-import") (part "ZENER-DIODESOD80C"))
    )
    (comp (ref "VD31")
      (value "ZENER-DIODESOD80C")
      (footprint "eagle-import:SOD80C")
      (libsource (lib "eagle-import") (part "ZENER-DIODESOD80C"))
    )
    (comp (ref "VD32")
      (value "ZENER-DIODESOD80C")
      (footprint "eagle-import:SOD80C")
      (libsource (lib "eagle-import") (part "ZENER-DIODESOD80C"))
    )
    (comp (ref "VD55")
      (value "ZENER-DIODESOD80C")
      (footprint "eagle-import:SOD80C")
      (libsource (lib "eagle-import") (part "ZENER-DIODESOD80C"))
    )
    (comp (ref "VT1")
      (value "BC849SMD")
      (footprint "eagle-import:SOT23-BEC")
      (libsource (lib "eagle-import") (part "BC849SMD"))
    )
    (comp (ref "VT2")
      (value "BC849SMD")
      (footprint "eagle-import:SOT23-BEC")
      (libsource (lib "eagle-import") (part "BC849SMD"))
    )
    (comp (ref "VT3")
      (value "BC849SMD")
      (footprint "eagle-import:SOT23-BEC")
      (libsource (lib "eagle-import") (part "BC849SMD"))
    )
    (comp (ref "VT4")
      (value "BC849SMD")
      (footprint "eagle-import:SOT23-BEC")
      (libsource (lib "eagle-import") (part "BC849SMD"))
    )
    (comp (ref "VT5")
      (value "BC849SMD")
      (footprint "eagle-import:SOT23-BEC")
      (libsource (lib "eagle-import") (part "BC849SMD"))
    )
    (comp (ref "VT6")
      (value "BC849SMD")
      (footprint "eagle-import:SOT23-BEC")
      (libsource (lib "eagle-import") (part "BC849SMD"))
    )
    (comp (ref "VT7")
      (value "BC849SMD")
      (footprint "eagle-import:SOT23-BEC")
      (libsource (lib "eagle-import") (part "BC849SMD"))
    )
    (comp (ref "VT8")
      (value "BC849SMD")
      (footprint "eagle-import:SOT23-BEC")
      (libsource (lib "eagle-import") (part "BC849SMD"))
    )
    (comp (ref "VT9")
      (value "BC849SMD")
      (footprint "eagle-import:SOT23-BEC")
      (libsource (lib "eagle-import") (part "BC849SMD"))
    )
    (comp (ref "VT10")
      (value "BC849SMD")
      (footprint "eagle-import:SOT23-BEC")
      (libsource (lib "eagle-import") (part "BC849SMD"))
    )
    (comp (ref "VT11")
      (value "BC849SMD")
      (footprint "eagle-import:SOT23-BEC")
      (libsource (lib "eagle-import") (part "BC849SMD"))
    )
    (comp (ref "VT12")
      (value "BC849SMD")
      (footprint "eagle-import:SOT23-BEC")
      (libsource (lib "eagle-import") (part "BC849SMD"))
    )
    (comp (ref "VT13")
      (value "BC849SMD")
      (footprint "eagle-import:SOT23-BEC")
      (libsource (lib "eagle-import") (part "BC849SMD"))
    )
    (comp (ref "VT14")
      (value "BC849SMD")
      (footprint "eagle-import:SOT23-BEC")
      (libsource (lib "eagle-import") (part "BC849SMD"))
    )
    (comp (ref "VT15")
      (value "BC849SMD")
      (footprint "eagle-import:SOT23-BEC")
      (libsource (lib "eagle-import") (part "BC849SMD"))
    )
    (comp (ref "VT16")
      (value "BC849SMD")
      (footprint "eagle-import:SOT23-BEC")
      (libsource (lib "eagle-import") (part "BC849SMD"))
    )
    (comp (ref "VT17")
      (value "BC849SMD")
      (footprint "eagle-import:SOT23-BEC")
      (libsource (lib "eagle-import") (part "BC849SMD"))
    )
    (comp (ref "VT18")
      (value "BC849SMD")
      (footprint "eagle-import:SOT23-BEC")
      (libsource (lib "eagle-import") (part "BC849SMD"))
    )
    (comp (ref "VT19")
      (value "BC849SMD")
      (footprint "eagle-import:SOT23-BEC")
      (libsource (lib "eagle-import") (part "BC849SMD"))
    )
    (comp (ref "VT20")
      (value "BC849SMD")
      (footprint "eagle-import:SOT23-BEC")
      (libsource (lib "eagle-import") (part "BC849SMD"))
    )
    (comp (ref "VT21")
      (value "BC849SMD")
      (footprint "eagle-import:SOT23-BEC")
      (libsource (lib "eagle-import") (part "BC849SMD"))
    )
    (comp (ref "VT22")
      (value "BC849SMD")
      (footprint "eagle-import:SOT23-BEC")
      (libsource (lib "eagle-import") (part "BC849SMD"))
    )
    (comp (ref "VT23")
      (value "BC849SMD")
      (footprint "eagle-import:SOT23-BEC")
      (libsource (lib "eagle-import") (part "BC849SMD"))
    )
    (comp (ref "VT24")
      (value "BC849SMD")
      (footprint "eagle-import:SOT23-BEC")
      (libsource (lib "eagle-import") (part "BC849SMD"))
    )
    (comp (ref "VT25")
      (value "BC849SMD")
      (footprint "eagle-import:SOT23-BEC")
      (libsource (lib "eagle-import") (part "BC849SMD"))
    )
    (comp (ref "VT26")
      (value "BC849SMD")
      (footprint "eagle-import:SOT23-BEC")
      (libsource (lib "eagle-import") (part "BC849SMD"))
    )
    (comp (ref "VT27")
      (value "BC849SMD")
      (footprint "eagle-import:SOT23-BEC")
      (libsource (lib "eagle-import") (part "BC849SMD"))
    )
    (comp (ref "VT28")
      (value "BC849SMD")
      (footprint "eagle-import:SOT23-BEC")
      (libsource (lib "eagle-import") (part "BC849SMD"))
    )
    (comp (ref "VT29")
      (value "BC849SMD")
      (footprint "eagle-import:SOT23-BEC")
      (libsource (lib "eagle-import") (part "BC849SMD"))
    )
    (comp (ref "VT30")
      (value "BC849SMD")
      (footprint "eagle-import:SOT23-BEC")
      (libsource (lib "eagle-import") (part "BC849SMD"))
    )
    (comp (ref "VT31")
      (value "BC849SMD")
      (footprint "eagle-import:SOT23-BEC")
      (libsource (lib "eagle-import") (part "BC849SMD"))
    )
    (comp (ref "VT32")
      (value "BC849SMD")
      (footprint "eagle-import:SOT23-BEC")
      (libsource (lib "eagle-import") (part "BC849SMD"))
    )
    (comp (ref "VT55")
      (value "BC849SMD")
      (footprint "eagle-import:SOT23-BEC")
      (libsource (lib "eagle-import") (part "BC849SMD"))
    )
    (comp (ref "BT1")
      (value "2032 3v")
      (footprint "eagle-import:BATTCOM_20MM_PTH")
      (libsource (lib "eagle-import") (part "BATTERY-20MM_PTH"))
    )
    (comp (ref "C3")
      (value "C-EUC0805")
      (footprint "eagle-import:C0805")
      (libsource (lib "eagle-import") (part "C-EUC0805"))
    )
    (comp (ref "C4")
      (value "C-EUC0805")
      (footprint "eagle-import:C0805")
      (libsource (lib "eagle-import") (part "C-EUC0805"))
    )
    (comp (ref "C5")
      (value "C-EUC0805")
      (footprint "eagle-import:C0805")
      (libsource (lib "eagle-import") (part "C-EUC0805"))
    )
    (comp (ref "C6")
      (value "C-EUC0805")
      (footprint "eagle-import:C0805")
      (libsource (lib "eagle-import") (part "C-EUC0805"))
    )
    (comp (ref "C7")
      (value "C-EUC0805")
      (footprint "eagle-import:C0805")
      (libsource (lib "eagle-import") (part "C-EUC0805"))
    )
    (comp (ref "C8")
      (value "C-EUC3225")
      (footprint "eagle-import:C3225")
      (libsource (lib "eagle-import") (part "C-EUC3225"))
    )
    (comp (ref "DD1A")
      (value "DS3231SOIC-16W")
      (footprint "eagle-import:SOIC-16W")
      (libsource (lib "eagle-import") (part "DS3231SOIC-16W"))
    )
    (comp (ref "DD1B")
      (value "DS1307")
      (footprint "eagle-import:DIL08")
      (libsource (lib "eagle-import") (part "DS1307"))
    )
    (comp (ref "DD2")
      (value "ATMEGA328P")
      (footprint "eagle-import:TQFP32-08")
      (fields (field (name "MPN") "ATMEGA8-16AU"))
      (libsource (lib "eagle-import") (part "MEGA8-AI"))
    )
    (comp (ref "ISP")
      (value "MA03-2")
      (footprint "eagle-import:MA03-2")
      (libsource (lib "eagle-import") (part "MA03-2"))
    )
    (comp (ref "J1")
      (value "R-EU_R1206")
      (footprint "eagle-import:R1206")
      (libsource (lib "eagle-import") (part "R-EU_R1206"))
    )
    (comp (ref "J2")
      (value "R-EU_R1206")
      (footprint "eagle-import:R1206")
      (libsource (lib "eagle-import") (part "R-EU_R1206"))
    )
    (comp (ref "J3")
      (value "J5MM")
      (footprint "eagle-import:05")
      (libsource (lib "eagle-import") (part "J5MM"))
    )
    (comp (ref "J4")
      (value "R-EU_R1206W")
      (footprint "eagle-import:R1206W")
      (libsource (lib "eagle-import") (part "R-EU_R1206W"))
    )
    (comp (ref "J5")
      (value "R-EU_R1206W")
      (footprint "eagle-import:R1206W")
      (libsource (lib "eagle-import") (part "R-EU_R1206W"))
    )
    (comp (ref "Q1")
      (value "CRYSTALHC49U70")
      (footprint "eagle-import:HC49U70")
      (fields (field (name "OC_FARNELL") "unknown"))
      (libsource (lib "eagle-import") (part "CRYSTALHC49U70"))
    )
    (comp (ref "R106")
      (value "10k")
      (footprint "eagle-import:R0805")
      (libsource (lib "eagle-import") (part "R-EU_R0805"))
    )
    (comp (ref "R107")
      (value "10k")
      (footprint "eagle-import:R0805")
      (libsource (lib "eagle-import") (part "R-EU_R0805"))
    )
    (comp (ref "R108")
      (value "10k")
      (footprint "eagle-import:R0805")
      (libsource (lib "eagle-import") (part "R-EU_R0805"))
    )
    (comp (ref "R109")
      (value "10k")
      (footprint "eagle-import:R0805")
      (libsource (lib "eagle-import") (part "R-EU_R0805"))
    )
    (comp (ref "R110")
      (value "10k")
      (footprint "eagle-import:R0805")
      (libsource (lib "eagle-import") (part "R-EU_R0805"))
    )
    (comp (ref "R113")
      (value "10k")
      (footprint "eagle-import:R0805")
      (libsource (lib "eagle-import") (part "R-EU_R0805"))
    )
    (comp (ref "SJ1") (value "SJ") (footprint "eagle-import:SJ") (libsource (lib "eagle-import") (part "SJ")))
    (comp (ref "Z1")
      (value "32768")
      (footprint "eagle-import:FC-12M")
      (libsource (lib "eagle-import") (part "FC-12M"))
    )
    (comp (ref "R65")
      (value "R-EU_R0805")
      (footprint "eagle-import:R0805")
      (libsource (lib "eagle-import") (part "R-EU_R0805"))
    )
    (comp (ref "R66")
      (value "R-EU_0207/12")
      (footprint "eagle-import:0207_12")
      (libsource (lib "eagle-import") (part "R-EU_0207/12"))
    )
    (comp (ref "R67")
      (value "R-EU_R0805")
      (footprint "eagle-import:R0805")
      (libsource (lib "eagle-import") (part "R-EU_R0805"))
    )
    (comp (ref "R68")
      (value "R-EU_0207/12")
      (footprint "eagle-import:0207_12")
      (libsource (lib "eagle-import") (part "R-EU_0207/12"))
    )
    (comp (ref "R69")
      (value "R-EU_R0805")
      (footprint "eagle-import:R0805")
      (libsource (lib "eagle-import") (part "R-EU_R0805"))
    )
    (comp (ref "R70")
      (value "R-EU_0207/12")
      (footprint "eagle-import:0207_12")
      (libsource (lib "eagle-import") (part "R-EU_0207/12"))
    )
    (comp (ref "R71")
      (value "R-EU_R0805")
      (footprint "eagle-import:R0805")
      (libsource (lib "eagle-import") (part "R-EU_R0805"))
    )
    (comp (ref "R72")
      (value "R-EU_0207/12")
      (footprint "eagle-import:0207_12")
      (libsource (lib "eagle-import") (part "R-EU_0207/12"))
    )
    (comp (ref "R73")
      (value "R-EU_R0805")
      (footprint "eagle-import:R0805")
      (libsource (lib "eagle-import") (part "R-EU_R0805"))
    )
    (comp (ref "R74")
      (value "R-EU_0207/12")
      (footprint "eagle-import:0207_12")
      (libsource (lib "eagle-import") (part "R-EU_0207/12"))
    )
    (comp (ref "R75")
      (value "R-EU_R1206W")
      (footprint "eagle-import:R1206W")
      (libsource (lib "eagle-import") (part "R-EU_R1206W"))
    )
    (comp (ref "R76")
      (value "R-EU_0207/10")
      (footprint "eagle-import:0207_10")
      (libsource (lib "eagle-import") (part "R-EU_0207/10"))
    )
    (comp (ref "R77")
      (value "R-EU_R0805")
      (footprint "eagle-import:R0805")
      (libsource (lib "eagle-import") (part "R-EU_R0805"))
    )
    (comp (ref "R79")
      (value "R-EU_R0805")
      (footprint "eagle-import:R0805")
      (libsource (lib "eagle-import") (part "R-EU_R0805"))
    )
    (comp (ref "R80")
      (value "R-EU_0207/12")
      (footprint "eagle-import:0207_12")
      (libsource (lib "eagle-import") (part "R-EU_0207/12"))
    )
    (comp (ref "R81")
      (value "R-EU_R0805")
      (footprint "eagle-import:R0805")
      (libsource (lib "eagle-import") (part "R-EU_R0805"))
    )
    (comp (ref "R82")
      (value "R-EU_0207/12")
      (footprint "eagle-import:0207_12")
      (libsource (lib "eagle-import") (part "R-EU_0207/12"))
    )
    (comp (ref "R83")
      (value "R-EU_R0805")
      (footprint "eagle-import:R0805")
      (libsource (lib "eagle-import") (part "R-EU_R0805"))
    )
    (comp (ref "R84")
      (value "R-EU_0207/12")
      (footprint "eagle-import:0207_12")
      (libsource (lib "eagle-import") (part "R-EU_0207/12"))
    )
    (comp (ref "R85")
      (value "R-EU_R0805")
      (footprint "eagle-import:R0805")
      (libsource (lib "eagle-import") (part "R-EU_R0805"))
    )
    (comp (ref "R86")
      (value "R-EU_0207/12")
      (footprint "eagle-import:0207_12")
      (libsource (lib "eagle-import") (part "R-EU_0207/12"))
    )
    (comp (ref "R87")
      (value "R-EU_R0805")
      (footprint "eagle-import:R0805")
      (libsource (lib "eagle-import") (part "R-EU_R0805"))
    )
    (comp (ref "R88")
      (value "R-EU_0207/12")
      (footprint "eagle-import:0207_12")
      (libsource (lib "eagle-import") (part "R-EU_0207/12"))
    )
    (comp (ref "R89")
      (value "R-EU_R0805")
      (footprint "eagle-import:R0805")
      (libsource (lib "eagle-import") (part "R-EU_R0805"))
    )
    (comp (ref "R90")
      (value "R-EU_0207/12")
      (footprint "eagle-import:0207_12")
      (libsource (lib "eagle-import") (part "R-EU_0207/12"))
    )
    (comp (ref "R91")
      (value "R-EU_0207/12")
      (footprint "eagle-import:0207_12")
      (libsource (lib "eagle-import") (part "R-EU_0207/12"))
    )
    (comp (ref "R92")
      (value "R-EU_0207/12")
      (footprint "eagle-import:0207_12")
      (libsource (lib "eagle-import") (part "R-EU_0207/12"))
    )
    (comp (ref "R93")
      (value "R-EU_R0805")
      (footprint "eagle-import:R0805")
      (libsource (lib "eagle-import") (part "R-EU_R0805"))
    )
    (comp (ref "R94")
      (value "R-EU_0207/12")
      (footprint "eagle-import:0207_12")
      (libsource (lib "eagle-import") (part "R-EU_0207/12"))
    )
    (comp (ref "R95")
      (value "R-EU_R0805")
      (footprint "eagle-import:R0805")
      (libsource (lib "eagle-import") (part "R-EU_R0805"))
    )
    (comp (ref "R96")
      (value "R-EU_0207/12")
      (footprint "eagle-import:0207_12")
      (libsource (lib "eagle-import") (part "R-EU_0207/12"))
    )
    (comp (ref "R97")
      (value "R-EU_R0805")
      (footprint "eagle-import:R0805")
      (libsource (lib "eagle-import") (part "R-EU_R0805"))
    )
    (comp (ref "R98")
      (value "R-EU_0207/12")
      (footprint "eagle-import:0207_12")
      (libsource (lib "eagle-import") (part "R-EU_0207/12"))
    )
    (comp (ref "R99")
      (value "R-EU_R0805")
      (footprint "eagle-import:R0805")
      (libsource (lib "eagle-import") (part "R-EU_R0805"))
    )
    (comp (ref "R100")
      (value "R-EU_0207/12")
      (footprint "eagle-import:0207_12")
      (libsource (lib "eagle-import") (part "R-EU_0207/12"))
    )
    (comp (ref "R101")
      (value "R-EU_R0805")
      (footprint "eagle-import:R0805")
      (libsource (lib "eagle-import") (part "R-EU_R0805"))
    )
    (comp (ref "R102")
      (value "R-EU_0207/12")
      (footprint "eagle-import:0207_12")
      (libsource (lib "eagle-import") (part "R-EU_0207/12"))
    )
    (comp (ref "R103")
      (value "R-EU_R0805")
      (footprint "eagle-import:R0805")
      (libsource (lib "eagle-import") (part "R-EU_R0805"))
    )
    (comp (ref "R104")
      (value "R-EU_0207/15")
      (footprint "eagle-import:0207_15")
      (libsource (lib "eagle-import") (part "R-EU_0207/15"))
    )
    (comp (ref "R105")
      (value "R-EU_R0805")
      (footprint "eagle-import:R0805")
      (libsource (lib "eagle-import") (part "R-EU_R0805"))
    )
    (comp (ref "R111")
      (value "R-EU_R0805")
      (footprint "eagle-import:R0805")
      (libsource (lib "eagle-import") (part "R-EU_R0805"))
    )
    (comp (ref "R112")
      (value "R-EU_M0805")
      (footprint "eagle-import:M0805")
      (libsource (lib "eagle-import") (part "R-EU_M0805"))
    )
    (comp (ref "R114")
      (value "R-EU_M0805")
      (footprint "eagle-import:M0805")
      (libsource (lib "eagle-import") (part "R-EU_M0805"))
    )
    (comp (ref "RE1")
      (value "PINHD-1X1")
      (footprint "eagle-import:1X01")
      (libsource (lib "eagle-import") (part "PINHD-1X1"))
    )
    (comp (ref "RE2")
      (value "PINHD-1X1")
      (footprint "eagle-import:1X01")
      (libsource (lib "eagle-import") (part "PINHD-1X1"))
    )
    (comp (ref "VD33")
      (value "ZENER-DIODESOD80C")
      (footprint "eagle-import:SOD80C")
      (libsource (lib "eagle-import") (part "ZENER-DIODESOD80C"))
    )
    (comp (ref "VD34")
      (value "ZENER-DIODESOD80C")
      (footprint "eagle-import:SOD80C")
      (libsource (lib "eagle-import") (part "ZENER-DIODESOD80C"))
    )
    (comp (ref "VD35")
      (value "ZENER-DIODESOD80C")
      (footprint "eagle-import:SOD80C")
      (libsource (lib "eagle-import") (part "ZENER-DIODESOD80C"))
    )
    (comp (ref "VD36")
      (value "ZENER-DIODESOD80C")
      (footprint "eagle-import:SOD80C")
      (libsource (lib "eagle-import") (part "ZENER-DIODESOD80C"))
    )
    (comp (ref "VD37")
      (value "ZENER-DIODESOD80C")
      (footprint "eagle-import:SOD80C")
      (libsource (lib "eagle-import") (part "ZENER-DIODESOD80C"))
    )
    (comp (ref "VD38")
      (value "ZENER-DIODESOD80C")
      (footprint "eagle-import:SOD80C")
      (libsource (lib "eagle-import") (part "ZENER-DIODESOD80C"))
    )
    (comp (ref "VD39")
      (value "ZENER-DIODESOD80C")
      (footprint "eagle-import:SOD80C")
      (libsource (lib "eagle-import") (part "ZENER-DIODESOD80C"))
    )
    (comp (ref "VD40")
      (value "ZENER-DIODESOD80C")
      (footprint "eagle-import:SOD80C")
      (libsource (lib "eagle-import") (part "ZENER-DIODESOD80C"))
    )
    (comp (ref "VD41")
      (value "ZENER-DIODESOD80C")
      (footprint "eagle-import:SOD80C")
      (libsource (lib "eagle-import") (part "ZENER-DIODESOD80C"))
    )
    (comp (ref "VD42")
      (value "ZENER-DIODESOD80C")
      (footprint "eagle-import:SOD80C")
      (libsource (lib "eagle-import") (part "ZENER-DIODESOD80C"))
    )
    (comp (ref "VD43")
      (value "ZENER-DIODESOD80C")
      (footprint "eagle-import:SOD80C")
      (libsource (lib "eagle-import") (part "ZENER-DIODESOD80C"))
    )
    (comp (ref "VD44")
      (value "ZENER-DIODESOD80C")
      (footprint "eagle-import:SOD80C")
      (libsource (lib "eagle-import") (part "ZENER-DIODESOD80C"))
    )
    (comp (ref "VD45")
      (value "ZENER-DIODESOD80C")
      (footprint "eagle-import:SOD80C")
      (libsource (lib "eagle-import") (part "ZENER-DIODESOD80C"))
    )
    (comp (ref "VD46")
      (value "ZENER-DIODESOD80C")
      (footprint "eagle-import:SOD80C")
      (libsource (lib "eagle-import") (part "ZENER-DIODESOD80C"))
    )
    (comp (ref "VD47")
      (value "ZENER-DIODESOD80C")
      (footprint "eagle-import:SOD80C")
      (libsource (lib "eagle-import") (part "ZENER-DIODESOD80C"))
    )
    (comp (ref "VD48")
      (value "ZENER-DIODESOD80C")
      (footprint "eagle-import:SOD80C")
      (libsource (lib "eagle-import") (part "ZENER-DIODESOD80C"))
    )
    (comp (ref "VD49")
      (value "ZENER-DIODESOD80C")
      (footprint "eagle-import:SOD80C")
      (libsource (lib "eagle-import") (part "ZENER-DIODESOD80C"))
    )
    (comp (ref "VD50")
      (value "ZENER-DIODESOD80C")
      (footprint "eagle-import:SOD80C")
      (libsource (lib "eagle-import") (part "ZENER-DIODESOD80C"))
    )
    (comp (ref "VD51")
      (value "ZENER-DIODESOD80C")
      (footprint "eagle-import:SOD80C")
      (libsource (lib "eagle-import") (part "ZENER-DIODESOD80C"))
    )
    (comp (ref "VD52")
      (value "ZENER-DIODESOD80C")
      (footprint "eagle-import:SOD80C")
      (libsource (lib "eagle-import") (part "ZENER-DIODESOD80C"))
    )
    (comp (ref "VD53")
      (value "ZENER-DIODESOD80C")
      (footprint "eagle-import:SOD80C")
      (libsource (lib "eagle-import") (part "ZENER-DIODESOD80C"))
    )
    (comp (ref "VD54")
      (value "ZENER-DIODESOD80C")
      (footprint "eagle-import:SOD80C")
      (libsource (lib "eagle-import") (part "ZENER-DIODESOD80C"))
    )
    (comp (ref "VT33")
      (value "BC849SMD")
      (footprint "eagle-import:SOT23-BEC")
      (libsource (lib "eagle-import") (part "BC849SMD"))
    )
    (comp (ref "VT34")
      (value "BC849SMD")
      (footprint "eagle-import:SOT23-BEC")
      (libsource (lib "eagle-import") (part "BC849SMD"))
    )
    (comp (ref "VT35")
      (value "BC849SMD")
      (footprint "eagle-import:SOT23-BEC")
      (libsource (lib "eagle-import") (part "BC849SMD"))
    )
    (comp (ref "VT36")
      (value "BC849SMD")
      (footprint "eagle-import:SOT23-BEC")
      (libsource (lib "eagle-import") (part "BC849SMD"))
    )
    (comp (ref "VT37")
      (value "BC849SMD")
      (footprint "eagle-import:SOT23-BEC")
      (libsource (lib "eagle-import") (part "BC849SMD"))
    )
    (comp (ref "VT38")
      (value "BC849SMD")
      (footprint "eagle-import:SOT23-BEC")
      (libsource (lib "eagle-import") (part "BC849SMD"))
    )
    (comp (ref "VT39")
      (value "BC849SMD")
      (footprint "eagle-import:SOT23-BEC")
      (libsource (lib "eagle-import") (part "BC849SMD"))
    )
    (comp (ref "VT40")
      (value "BC849SMD")
      (footprint "eagle-import:SOT23-BEC")
      (libsource (lib "eagle-import") (part "BC849SMD"))
    )
    (comp (ref "VT41")
      (value "BC849SMD")
      (footprint "eagle-import:SOT23-BEC")
      (libsource (lib "eagle-import") (part "BC849SMD"))
    )
    (comp (ref "VT42")
      (value "BC849SMD")
      (footprint "eagle-import:SOT23-BEC")
      (libsource (lib "eagle-import") (part "BC849SMD"))
    )
    (comp (ref "VT43")
      (value "BC849SMD")
      (footprint "eagle-import:SOT23-BEC")
      (libsource (lib "eagle-import") (part "BC849SMD"))
    )
    (comp (ref "VT44")
      (value "BC849SMD")
      (footprint "eagle-import:SOT23-BEC")
      (libsource (lib "eagle-import") (part "BC849SMD"))
    )
    (comp (ref "VT45")
      (value "BC849SMD")
      (footprint "eagle-import:SOT23-BEC")
      (libsource (lib "eagle-import") (part "BC849SMD"))
    )
    (comp (ref "VT46")
      (value "BC849SMD")
      (footprint "eagle-import:SOT23-BEC")
      (libsource (lib "eagle-import") (part "BC849SMD"))
    )
    (comp (ref "VT47")
      (value "BC849SMD")
      (footprint "eagle-import:SOT23-BEC")
      (libsource (lib "eagle-import") (part "BC849SMD"))
    )
    (comp (ref "VT48")
      (value "BC849SMD")
      (footprint "eagle-import:SOT23-BEC")
      (libsource (lib "eagle-import") (part "BC849SMD"))
    )
    (comp (ref "VT49")
      (value "BC849SMD")
      (footprint "eagle-import:SOT23-BEC")
      (libsource (lib "eagle-import") (part "BC849SMD"))
    )
    (comp (ref "VT50")
      (value "BC849SMD")
      (footprint "eagle-import:SOT23-BEC")
      (libsource (lib "eagle-import") (part "BC849SMD"))
    )
    (comp (ref "VT51")
      (value "BC849SMD")
      (footprint "eagle-import:SOT23-BEC")
      (libsource (lib "eagle-import") (part "BC849SMD"))
    )
    (comp (ref "VT52")
      (value "BC849SMD")
      (footprint "eagle-import:SOT23-BEC")
      (libsource (lib "eagle-import") (part "BC849SMD"))
    )
    (comp (ref "VT53")
      (value "BC849SMD")
      (footprint "eagle-import:SOT23-BEC")
      (libsource (lib "eagle-import") (part "BC849SMD"))
    )
    (comp (ref "VT54")
      (value "BC849SMD")
      (footprint "eagle-import:SOT23-BEC")
      (libsource (lib "eagle-import") (part "BC849SMD"))
    )
    (comp (ref "C1")
      (value "C-EUC0805")
      (footprint "eagle-import:C0805")
      (libsource (lib "eagle-import") (part "C-EUC0805"))
    )
    (comp (ref "C2")
      (value "C-EUC0805")
      (footprint "eagle-import:C0805")
      (libsource (lib "eagle-import") (part "C-EUC0805"))
    )
    (comp (ref "C9")
      (value "C-EUC0805")
      (footprint "eagle-import:C0805")
      (libsource (lib "eagle-import") (part "C-EUC0805"))
    )
    (comp (ref "C10")
      (value "C-EUC0805")
      (footprint "eagle-import:C0805")
      (libsource (lib "eagle-import") (part "C-EUC0805"))
    )
    (comp (ref "C11")
      (value "C-EUC0805")
      (footprint "eagle-import:C0805")
      (libsource (lib "eagle-import") (part "C-EUC0805"))
    )
    (comp (ref "C12")
      (value "C-EUC0805")
      (footprint "eagle-import:C0805")
      (libsource (lib "eagle-import") (part "C-EUC0805"))
    )
    (comp (ref "C13")
      (value "C-EUC0805")
      (footprint "eagle-import:C0805")
      (libsource (lib "eagle-import") (part "C-EUC0805"))
    )
    (comp (ref "IC1")
      (value "74HC595D")
      (footprint "eagle-import:SO16")
      (libsource (lib "eagle-import") (part "74595DHC"))
    )
    (comp (ref "IC2")
      (value "74HC595D")
      (footprint "eagle-import:SO16")
      (libsource (lib "eagle-import") (part "74595DHC"))
    )
    (comp (ref "IC3")
      (value "74HC595D")
      (footprint "eagle-import:SO16")
      (libsource (lib "eagle-import") (part "74595DHC"))
    )
    (comp (ref "IC4")
      (value "74HC595D")
      (footprint "eagle-import:SO16")
      (libsource (lib "eagle-import") (part "74595DHC"))
    )
    (comp (ref "IC5")
      (value "74HC595D")
      (footprint "eagle-import:SO16")
      (libsource (lib "eagle-import") (part "74595DHC"))
    )
    (comp (ref "IC6")
      (value "74HC595D")
      (footprint "eagle-import:SO16")
      (libsource (lib "eagle-import") (part "74595DHC"))
    )
    (comp (ref "IC7")
      (value "74HC595D")
      (footprint "eagle-import:SO16")
      (libsource (lib "eagle-import") (part "74595DHC"))
    )
    (comp (ref "J6")
      (value "R-EU_R1206W")
      (footprint "eagle-import:R1206W")
      (libsource (lib "eagle-import") (part "R-EU_R1206W"))
    )
  )
  (nets
    (net (code "1") (name "+5V") (class "Default")
      (node (ref "C1") (pin "1") (pinfunction "1_1") (pintype "passive"))
      (node (ref "C10") (pin "1") (pinfunction "1_1") (pintype "passive"))
      (node (ref "C11") (pin "1") (pinfunction "1_1") (pintype "passive"))
      (node (ref "C12") (pin "1") (pinfunction "1_1") (pintype "passive"))
      (node (ref "C13") (pin "1") (pinfunction "1_1") (pintype "passive"))
      (node (ref "C2") (pin "1") (pinfunction "1_1") (pintype "passive"))
      (node (ref "C5") (pin "1") (pinfunction "1_1") (pintype "passive"))
      (node (ref "C6") (pin "1") (pinfunction "1_1") (pintype "passive"))
      (node (ref "C7") (pin "1") (pinfunction "1_1") (pintype "passive"))
      (node (ref "C9") (pin "1") (pinfunction "1_1") (pintype "passive"))
      (node (ref "DD1A") (pin "2") (pinfunction "VCC_2") (pintype "bidirectional"))
      (node (ref "DD1B") (pin "8") (pinfunction "VCC_8") (pintype "power_in"))
      (node (ref "DD2") (pin "4") (pinfunction "VCC_4") (pintype "power_in"))
      (node (ref "DD2") (pin "6") (pinfunction "VCC_6") (pintype "power_in"))
      (node (ref "IC1") (pin "10") (pinfunction "SCL_10") (pintype "input"))
      (node (ref "IC1") (pin "16") (pinfunction "VCC_16") (pintype "power_in"))
      (node (ref "IC2") (pin "10") (pinfunction "SCL_10") (pintype "input"))
      (node (ref "IC2") (pin "16") (pinfunction "VCC_16") (pintype "power_in"))
      (node (ref "IC3") (pin "10") (pinfunction "SCL_10") (pintype "input"))
      (node (ref "IC3") (pin "16") (pinfunction "VCC_16") (pintype "power_in"))
      (node (ref "IC4") (pin "10") (pinfunction "SCL_10") (pintype "input"))
      (node (ref "IC4") (pin "16") (pinfunction "VCC_16") (pintype "power_in"))
      (node (ref "IC5") (pin "10") (pinfunction "SCL_10") (pintype "input"))
      (node (ref "IC5") (pin "16") (pinfunction "VCC_16") (pintype "power_in"))
      (node (ref "IC6") (pin "10") (pinfunction "SCL_10") (pintype "input"))
      (node (ref "IC6") (pin "16") (pinfunction "VCC_16") (pintype "power_in"))
      (node (ref "IC7") (pin "10") (pinfunction "SCL_10") (pintype "input"))
      (node (ref "IC7") (pin "16") (pinfunction "VCC_16") (pintype "power_in"))
      (node (ref "J1") (pin "2") (pinfunction "2_2") (pintype "passive"))
      (node (ref "R106") (pin "2") (pinfunction "2_2") (pintype "passive"))
      (node (ref "R107") (pin "2") (pinfunction "2_2") (pintype "passive"))
      (node (ref "R108") (pin "2") (pinfunction "2_2") (pintype "passive"))
      (node (ref "R109") (pin "2") (pinfunction "2_2") (pintype "passive"))
      (node (ref "R110") (pin "2") (pinfunction "2_2") (pintype "passive"))
      (node (ref "R113") (pin "2") (pinfunction "2_2") (pintype "passive"))
    )
    (net (code "2") (name "+100V") (class "Default")
      (node (ref "N1") (pin "A") (pinfunction "A_A") (pintype "bidirectional"))
      (node (ref "N10") (pin "A") (pinfunction "A_A") (pintype "bidirectional"))
      (node (ref "N11") (pin "A") (pinfunction "A_A") (pintype "bidirectional"))
      (node (ref "N12") (pin "A") (pinfunction "A_A") (pintype "bidirectional"))
      (node (ref "N13") (pin "A") (pinfunction "A_A") (pintype "bidirectional"))
      (node (ref "N14") (pin "A") (pinfunction "A_A") (pintype "bidirectional"))
      (node (ref "N15") (pin "A") (pinfunction "A_A") (pintype "bidirectional"))
      (node (ref "N16") (pin "A") (pinfunction "A_A") (pintype "bidirectional"))
      (node (ref "N17") (pin "A") (pinfunction "A_A") (pintype "bidirectional"))
      (node (ref "N18") (pin "A") (pinfunction "A_A") (pintype "bidirectional"))
      (node (ref "N19") (pin "A") (pinfunction "A_A") (pintype "bidirectional"))
      (node (ref "N2") (pin "A") (pinfunction "A_A") (pintype "bidirectional"))
      (node (ref "N20") (pin "A") (pinfunction "A_A") (pintype "bidirectional"))
      (node (ref "N21") (pin "A") (pinfunction "A_A") (pintype "bidirectional"))
      (node (ref "N22") (pin "A") (pinfunction "A_A") (pintype "bidirectional"))
      (node (ref "N23") (pin "A") (pinfunction "A_A") (pintype "bidirectional"))
      (node (ref "N24") (pin "A") (pinfunction "A_A") (pintype "bidirectional"))
      (node (ref "N25") (pin "A") (pinfunction "A_A") (pintype "bidirectional"))
      (node (ref "N27") (pin "A") (pinfunction "A_A") (pintype "bidirectional"))
      (node (ref "N28") (pin "A") (pinfunction "A_A") (pintype "bidirectional"))
      (node (ref "N29") (pin "A") (pinfunction "A_A") (pintype "bidirectional"))
      (node (ref "N3") (pin "A") (pinfunction "A_A") (pintype "bidirectional"))
      (node (ref "N30") (pin "A") (pinfunction "A_A") (pintype "bidirectional"))
      (node (ref "N31") (pin "A") (pinfunction "A_A") (pintype "bidirectional"))
      (node (ref "N32") (pin "A") (pinfunction "A_A") (pintype "bidirectional"))
      (node (ref "N33") (pin "A") (pinfunction "A_A") (pintype "bidirectional"))
      (node (ref "N34") (pin "A") (pinfunction "A_A") (pintype "bidirectional"))
      (node (ref "N35") (pin "A") (pinfunction "A_A") (pintype "bidirectional"))
      (node (ref "N36") (pin "A") (pinfunction "A_A") (pintype "bidirectional"))
      (node (ref "N37") (pin "A") (pinfunction "A_A") (pintype "bidirectional"))
      (node (ref "N38") (pin "A") (pinfunction "A_A") (pintype "bidirectional"))
      (node (ref "N39") (pin "A") (pinfunction "A_A") (pintype "bidirectional"))
      (node (ref "N4") (pin "A") (pinfunction "A_A") (pintype "bidirectional"))
      (node (ref "N40") (pin "A") (pinfunction "A_A") (pintype "bidirectional"))
      (node (ref "N41") (pin "A") (pinfunction "A_A") (pintype "bidirectional"))
      (node (ref "N42") (pin "A") (pinfunction "A_A") (pintype "bidirectional"))
      (node (ref "N43") (pin "A") (pinfunction "A_A") (pintype "bidirectional"))
      (node (ref "N44") (pin "A") (pinfunction "A_A") (pintype "bidirectional"))
      (node (ref "N45") (pin "A") (pinfunction "A_A") (pintype "bidirectional"))
      (node (ref "N46") (pin "A") (pinfunction "A_A") (pintype "bidirectional"))
      (node (ref "N47") (pin "A") (pinfunction "A_A") (pintype "bidirectional"))
      (node (ref "N48") (pin "A") (pinfunction "A_A") (pintype "bidirectional"))
      (node (ref "N49") (pin "A") (pinfunction "A_A") (pintype "bidirectional"))
      (node (ref "N5") (pin "A") (pinfunction "A_A") (pintype "bidirectional"))
      (node (ref "N50") (pin "A") (pinfunction "A_A") (pintype "bidirectional"))
      (node (ref "N51") (pin "A") (pinfunction "A_A") (pintype "bidirectional"))
      (node (ref "N52") (pin "A") (pinfunction "A_A") (pintype "bidirectional"))
      (node (ref "N53") (pin "A") (pinfunction "A_A") (pintype "bidirectional"))
      (node (ref "N54") (pin "A") (pinfunction "A_A") (pintype "bidirectional"))
      (node (ref "N6") (pin "A") (pinfunction "A_A") (pintype "bidirectional"))
      (node (ref "N7") (pin "A") (pinfunction "A_A") (pintype "bidirectional"))
      (node (ref "N8") (pin "A") (pinfunction "A_A") (pintype "bidirectional"))
      (node (ref "N9") (pin "A") (pinfunction "A_A") (pintype "bidirectional"))
      (node (ref "R78") (pin "2") (pinfunction "2_2") (pintype "passive"))
    )
    (net (code "3") (name "A1") (class "Default")
      (node (ref "N42") (pin "K") (pinfunction "K_K") (pintype "bidirectional"))
      (node (ref "R2") (pin "2") (pinfunction "2_2") (pintype "passive"))
    )
    (net (code "4") (name "A2") (class "Default")
      (node (ref "N43") (pin "K") (pinfunction "K_K") (pintype "bidirectional"))
      (node (ref "R4") (pin "2") (pinfunction "2_2") (pintype "passive"))
    )
    (net (code "5") (name "A3") (class "Default")
      (node (ref "N44") (pin "K") (pinfunction "K_K") (pintype "bidirectional"))
      (node (ref "R6") (pin "2") (pinfunction "2_2") (pintype "passive"))
    )
    (net (code "6") (name "A4") (class "Default")
      (node (ref "N45") (pin "K") (pinfunction "K_K") (pintype "bidirectional"))
      (node (ref "R8") (pin "2") (pinfunction "2_2") (pintype "passive"))
    )
    (net (code "7") (name "A5") (class "Default")
      (node (ref "N46") (pin "K") (pinfunction "K_K") (pintype "bidirectional"))
      (node (ref "R10") (pin "2") (pinfunction "2_2") (pintype "passive"))
    )
    (net (code "8") (name "A6") (class "Default")
      (node (ref "N47") (pin "K") (pinfunction "K_K") (pintype "bidirectional"))
      (node (ref "R12") (pin "2") (pinfunction "2_2") (pintype "passive"))
    )
    (net (code "9") (name "A7") (class "Default")
      (node (ref "N48") (pin "K") (pinfunction "K_K") (pintype "bidirectional"))
      (node (ref "R14") (pin "2") (pinfunction "2_2") (pintype "passive"))
    )
    (net (code "10") (name "A8") (class "Default")
      (node (ref "N49") (pin "K") (pinfunction "K_K") (pintype "bidirectional"))
      (node (ref "R16") (pin "2") (pinfunction "2_2") (pintype "passive"))
    )
    (net (code "11") (name "A9") (class "Default")
      (node (ref "N50") (pin "K") (pinfunction "K_K") (pintype "bidirectional"))
      (node (ref "R18") (pin "2") (pinfunction "2_2") (pintype "passive"))
    )
    (net (code "12") (name "A10") (class "Default")
      (node (ref "N51") (pin "K") (pinfunction "K_K") (pintype "bidirectional"))
      (node (ref "R20") (pin "2") (pinfunction "2_2") (pintype "passive"))
    )
    (net (code "13") (name "A11") (class "Default")
      (node (ref "N52") (pin "K") (pinfunction "K_K") (pintype "bidirectional"))
      (node (ref "R22") (pin "2") (pinfunction "2_2") (pintype "passive"))
    )
    (net (code "14") (name "A12") (class "Default")
      (node (ref "N53") (pin "K") (pinfunction "K_K") (pintype "bidirectional"))
      (node (ref "R24") (pin "2") (pinfunction "2_2") (pintype "passive"))
    )
    (net (code "15") (name "A13") (class "Default")
      (node (ref "N54") (pin "K") (pinfunction "K_K") (pintype "bidirectional"))
      (node (ref "R26") (pin "2") (pinfunction "2_2") (pintype "passive"))
    )
    (net (code "16") (name "AVCC") (class "Default")
      (node (ref "DD2") (pin "18") (pinfunction "AVCC_18") (pintype "power_in"))
    )
    (net (code "17") (name "B1") (class "Default")
      (node (ref "N29") (pin "K") (pinfunction "K_K") (pintype "bidirectional"))
      (node (ref "R28") (pin "2") (pinfunction "2_2") (pintype "passive"))
    )
    (net (code "18") (name "B2") (class "Default")
      (node (ref "N30") (pin "K") (pinfunction "K_K") (pintype "bidirectional"))
      (node (ref "R30") (pin "2") (pinfunction "2_2") (pintype "passive"))
    )
    (net (code "19") (name "B3") (class "Default")
      (node (ref "N31") (pin "K") (pinfunction "K_K") (pintype "bidirectional"))
      (node (ref "R32") (pin "2") (pinfunction "2_2") (pintype "passive"))
    )
    (net (code "20") (name "B4") (class "Default")
      (node (ref "N32") (pin "K") (pinfunction "K_K") (pintype "bidirectional"))
      (node (ref "R34") (pin "2") (pinfunction "2_2") (pintype "passive"))
    )
    (net (code "21") (name "B5") (class "Default")
      (node (ref "N33") (pin "K") (pinfunction "K_K") (pintype "bidirectional"))
      (node (ref "R36") (pin "2") (pinfunction "2_2") (pintype "passive"))
    )
    (net (code "22") (name "B6") (class "Default")
      (node (ref "N34") (pin "K") (pinfunction "K_K") (pintype "bidirectional"))
      (node (ref "R38") (pin "2") (pinfunction "2_2") (pintype "passive"))
    )
    (net (code "23") (name "B7") (class "Default")
      (node (ref "N35") (pin "K") (pinfunction "K_K") (pintype "bidirectional"))
      (node (ref "R40") (pin "2") (pinfunction "2_2") (pintype "passive"))
    )
    (net (code "24") (name "B8") (class "Default")
      (node (ref "N36") (pin "K") (pinfunction "K_K") (pintype "bidirectional"))
      (node (ref "R42") (pin "2") (pinfunction "2_2") (pintype "passive"))
    )
    (net (code "25") (name "B9") (class "Default")
      (node (ref "N37") (pin "K") (pinfunction "K_K") (pintype "bidirectional"))
      (node (ref "R44") (pin "2") (pinfunction "2_2") (pintype "passive"))
    )
    (net (code "26") (name "B10") (class "Default")
      (node (ref "N38") (pin "K") (pinfunction "K_K") (pintype "bidirectional"))
      (node (ref "R46") (pin "2") (pinfunction "2_2") (pintype "passive"))
    )
    (net (code "27") (name "B11") (class "Default")
      (node (ref "N39") (pin "K") (pinfunction "K_K") (pintype "bidirectional"))
      (node (ref "R48") (pin "2") (pinfunction "2_2") (pintype "passive"))
    )
    (net (code "28") (name "B12") (class "Default")
      (node (ref "N40") (pin "K") (pinfunction "K_K") (pintype "bidirectional"))
      (node (ref "R116") (pin "2") (pinfunction "2_2") (pintype "passive"))
      (node (ref "R50") (pin "2") (pinfunction "2_2") (pintype "passive"))
    )
    (net (code "29") (name "B13") (class "Default")
      (node (ref "N41") (pin "K") (pinfunction "K_K") (pintype "bidirectional"))
      (node (ref "R52") (pin "2") (pinfunction "2_2") (pintype "passive"))
    )
    (net (code "30") (name "C1") (class "Default")
      (node (ref "N14") (pin "K") (pinfunction "K_K") (pintype "bidirectional"))
      (node (ref "R54") (pin "2") (pinfunction "2_2") (pintype "passive"))
    )
    (net (code "31") (name "C2") (class "Default")
      (node (ref "N15") (pin "K") (pinfunction "K_K") (pintype "bidirectional"))
      (node (ref "R56") (pin "2") (pinfunction "2_2") (pintype "passive"))
    )
    (net (code "32") (name "C3") (class "Default")
      (node (ref "N16") (pin "K") (pinfunction "K_K") (pintype "bidirectional"))
      (node (ref "R58") (pin "2") (pinfunction "2_2") (pintype "passive"))
    )
    (net (code "33") (name "C4") (class "Default")
      (node (ref "N17") (pin "K") (pinfunction "K_K") (pintype "bidirectional"))
      (node (ref "R60") (pin "2") (pinfunction "2_2") (pintype "passive"))
    )
    (net (code "34") (name "C5") (class "Default")
      (node (ref "N18") (pin "K") (pinfunction "K_K") (pintype "bidirectional"))
      (node (ref "R62") (pin "2") (pinfunction "2_2") (pintype "passive"))
    )
    (net (code "35") (name "C6") (class "Default")
      (node (ref "N19") (pin "K") (pinfunction "K_K") (pintype "bidirectional"))
      (node (ref "R64") (pin "2") (pinfunction "2_2") (pintype "passive"))
    )
    (net (code "36") (name "C7") (class "Default")
      (node (ref "N20") (pin "K") (pinfunction "K_K") (pintype "bidirectional"))
      (node (ref "R66") (pin "2") (pinfunction "2_2") (pintype "passive"))
    )
    (net (code "37") (name "C8") (class "Default")
      (node (ref "N21") (pin "K") (pinfunction "K_K") (pintype "bidirectional"))
      (node (ref "R68") (pin "2") (pinfunction "2_2") (pintype "passive"))
    )
    (net (code "38") (name "C9") (class "Default")
      (node (ref "N22") (pin "K") (pinfunction "K_K") (pintype "bidirectional"))
      (node (ref "R70") (pin "2") (pinfunction "2_2") (pintype "passive"))
    )
    (net (code "39") (name "C10") (class "Default")
      (node (ref "N23") (pin "K") (pinfunction "K_K") (pintype "bidirectional"))
      (node (ref "R72") (pin "2") (pinfunction "2_2") (pintype "passive"))
    )
    (net (code "40") (name "C11") (class "Default")
      (node (ref "N24") (pin "K") (pinfunction "K_K") (pintype "bidirectional"))
      (node (ref "R74") (pin "2") (pinfunction "2_2") (pintype "passive"))
    )
    (net (code "41") (name "C12") (class "Default")
      (node (ref "N25") (pin "K") (pinfunction "K_K") (pintype "bidirectional"))
      (node (ref "R76") (pin "2") (pinfunction "2_2") (pintype "passive"))
    )
    (net (code "42") (name "C13") (class "Default")
      (node (ref "N26") (pin "K") (pinfunction "K_K") (pintype "bidirectional"))
      (node (ref "VT39") (pin "C") (pinfunction "C_C") (pintype "passive"))
    )
    (net (code "43") (name "D1") (class "Default")
      (node (ref "N1") (pin "K") (pinfunction "K_K") (pintype "bidirectional"))
      (node (ref "R80") (pin "2") (pinfunction "2_2") (pintype "passive"))
    )
    (net (code "44") (name "D2") (class "Default")
      (node (ref "N2") (pin "K") (pinfunction "K_K") (pintype "bidirectional"))
      (node (ref "R82") (pin "2") (pinfunction "2_2") (pintype "passive"))
    )
    (net (code "45") (name "D3") (class "Default")
      (node (ref "N3") (pin "K") (pinfunction "K_K") (pintype "bidirectional"))
      (node (ref "R84") (pin "2") (pinfunction "2_2") (pintype "passive"))
    )
    (net (code "46") (name "D4") (class "Default")
      (node (ref "N4") (pin "K") (pinfunction "K_K") (pintype "bidirectional"))
      (node (ref "R86") (pin "2") (pinfunction "2_2") (pintype "passive"))
    )
    (net (code "47") (name "D5") (class "Default")
      (node (ref "N5") (pin "K") (pinfunction "K_K") (pintype "bidirectional"))
      (node (ref "R88") (pin "2") (pinfunction "2_2") (pintype "passive"))
    )
    (net (code "48") (name "D6") (class "Default")
      (node (ref "N6") (pin "K") (pinfunction "K_K") (pintype "bidirectional"))
      (node (ref "R90") (pin "2") (pinfunction "2_2") (pintype "passive"))
    )
    (net (code "49") (name "D7") (class "Default")
      (node (ref "N7") (pin "K") (pinfunction "K_K") (pintype "bidirectional"))
      (node (ref "R92") (pin "2") (pinfunction "2_2") (pintype "passive"))
    )
    (net (code "50") (name "D8") (class "Default")
      (node (ref "N8") (pin "K") (pinfunction "K_K") (pintype "bidirectional"))
      (node (ref "R94") (pin "2") (pinfunction "2_2") (pintype "passive"))
    )
    (net (code "51") (name "D9") (class "Default")
      (node (ref "N9") (pin "K") (pinfunction "K_K") (pintype "bidirectional"))
      (node (ref "R96") (pin "2") (pinfunction "2_2") (pintype "passive"))
    )
    (net (code "52") (name "D10") (class "Default")
      (node (ref "N10") (pin "K") (pinfunction "K_K") (pintype "bidirectional"))
      (node (ref "R98") (pin "2") (pinfunction "2_2") (pintype "passive"))
    )
    (net (code "53") (name "D11") (class "Default")
      (node (ref "N11") (pin "K") (pinfunction "K_K") (pintype "bidirectional"))
      (node (ref "R100") (pin "2") (pinfunction "2_2") (pintype "passive"))
    )
    (net (code "54") (name "D12") (class "Default")
      (node (ref "N12") (pin "K") (pinfunction "K_K") (pintype "bidirectional"))
      (node (ref "R102") (pin "2") (pinfunction "2_2") (pintype "passive"))
    )
    (net (code "55") (name "D13") (class "Default")
      (node (ref "N13") (pin "K") (pinfunction "K_K") (pintype "bidirectional"))
      (node (ref "R104") (pin "2") (pinfunction "2_2") (pintype "passive"))
    )
    (net (code "56") (name "E1") (class "Default")
      (node (ref "N27") (pin "K") (pinfunction "K_K") (pintype "bidirectional"))
      (node (ref "R112") (pin "2") (pinfunction "2_2") (pintype "passive"))
    )
    (net (code "57") (name "E2") (class "Default")
      (node (ref "N28") (pin "K") (pinfunction "K_K") (pintype "bidirectional"))
      (node (ref "R114") (pin "2") (pinfunction "2_2") (pintype "passive"))
    )
    (net (code "58") (name "GND") (class "Default")
      (node (ref "BT1") (pin "2") (pinfunction "-_2") (pintype "power_in"))
      (node (ref "C1") (pin "2") (pinfunction "2_2") (pintype "passive"))
      (node (ref "C10") (pin "2") (pinfunction "2_2") (pintype "passive"))
      (node (ref "C11") (pin "2") (pinfunction "2_2") (pintype "passive"))
      (node (ref "C12") (pin "2") (pinfunction "2_2") (pintype "passive"))
      (node (ref "C13") (pin "2") (pinfunction "2_2") (pintype "passive"))
      (node (ref "C2") (pin "2") (pinfunction "2_2") (pintype "passive"))
      (node (ref "C5") (pin "2") (pinfunction "2_2") (pintype "passive"))
      (node (ref "C6") (pin "2") (pinfunction "2_2") (pintype "passive"))
      (node (ref "C7") (pin "2") (pinfunction "2_2") (pintype "passive"))
      (node (ref "C8") (pin "2") (pinfunction "2_2") (pintype "passive"))
      (node (ref "C9") (pin "2") (pinfunction "2_2") (pintype "passive"))
      (node (ref "DD1A") (pin "10") (pinfunction "NC_10") (pintype "bidirectional"))
      (node (ref "DD1A") (pin "11") (pinfunction "NC_11") (pintype "bidirectional"))
      (node (ref "DD1A") (pin "12") (pinfunction "NC_12") (pintype "bidirectional"))
      (node (ref "DD1A") (pin "13") (pinfunction "GND_13") (pintype "bidirectional"))
      (node (ref "DD1A") (pin "5") (pinfunction "NC_5") (pintype "bidirectional"))
      (node (ref "DD1A") (pin "6") (pinfunction "NC_6") (pintype "bidirectional"))
      (node (ref "DD1A") (pin "7") (pinfunction "NC_7") (pintype "bidirectional"))
      (node (ref "DD1A") (pin "8") (pinfunction "NC_8") (pintype "bidirectional"))
      (node (ref "DD1A") (pin "9") (pinfunction "NC_9") (pintype "bidirectional"))
      (node (ref "DD1B") (pin "4") (pinfunction "GND_4") (pintype "power_in"))
      (node (ref "DD2") (pin "21") (pinfunction "GND_21") (pintype "power_in"))
      (node (ref "DD2") (pin "3") (pinfunction "GND_3") (pintype "power_in"))
      (node (ref "DD2") (pin "5") (pinfunction "GND_5") (pintype "power_in"))
      (node (ref "IC1") (pin "13") (pinfunction "G_13") (pintype "input"))
      (node (ref "IC1") (pin "8") (pinfunction "GND_8") (pintype "power_in"))
      (node (ref "IC2") (pin "13") (pinfunction "G_13") (pintype "input"))
      (node (ref "IC2") (pin "8") (pinfunction "GND_8") (pintype "power_in"))
      (node (ref "IC3") (pin "13") (pinfunction "G_13") (pintype "input"))
      (node (ref "IC3") (pin "8") (pinfunction "GND_8") (pintype "power_in"))
      (node (ref "IC4") (pin "13") (pinfunction "G_13") (pintype "input"))
      (node (ref "IC4") (pin "8") (pinfunction "GND_8") (pintype "power_in"))
      (node (ref "IC5") (pin "13") (pinfunction "G_13") (pintype "input"))
      (node (ref "IC5") (pin "8") (pinfunction "GND_8") (pintype "power_in"))
      (node (ref "IC6") (pin "13") (pinfunction "G_13") (pintype "input"))
      (node (ref "IC6") (pin "8") (pinfunction "GND_8") (pintype "power_in"))
      (node (ref "IC7") (pin "13") (pinfunction "G_13") (pintype "input"))
      (node (ref "IC7") (pin "8") (pinfunction "GND_8") (pintype "power_in"))
      (node (ref "ISP") (pin "6") (pinfunction "6_6") (pintype "passive"))
      (node (ref "J2") (pin "1") (pinfunction "1_1") (pintype "passive"))
      (node (ref "J3") (pin "1") (pinfunction "1_1") (pintype "passive"))
      (node (ref "J3") (pin "2") (pinfunction "2_2") (pintype "passive"))
      (node (ref "SJ1") (pin "1") (pinfunction "1_1") (pintype "passive"))
      (node (ref "SJ1") (pin "2") (pinfunction "2_2") (pintype "passive"))
      (node (ref "VD1") (pin "A") (pinfunction "A_A") (pintype "passive"))
      (node (ref "VD10") (pin "A") (pinfunction "A_A") (pintype "passive"))
      (node (ref "VD11") (pin "A") (pinfunction "A_A") (pintype "passive"))
      (node (ref "VD12") (pin "A") (pinfunction "A_A") (pintype "passive"))
      (node (ref "VD13") (pin "A") (pinfunction "A_A") (pintype "passive"))
      (node (ref "VD14") (pin "A") (pinfunction "A_A") (pintype "passive"))
      (node (ref "VD15") (pin "A") (pinfunction "A_A") (pintype "passive"))
      (node (ref "VD16") (pin "A") (pinfunction "A_A") (pintype "passive"))
      (node (ref "VD17") (pin "A") (pinfunction "A_A") (pintype "passive"))
      (node (ref "VD18") (pin "A") (pinfunction "A_A") (pintype "passive"))
      (node (ref "VD19") (pin "A") (pinfunction "A_A") (pintype "passive"))
      (node (ref "VD2") (pin "A") (pinfunction "A_A") (pintype "passive"))
      (node (ref "VD20") (pin "A") (pinfunction "A_A") (pintype "passive"))
      (node (ref "VD21") (pin "A") (pinfunction "A_A") (pintype "passive"))
      (node (ref "VD22") (pin "A") (pinfunction "A_A") (pintype "passive"))
      (node (ref "VD23") (pin "A") (pinfunction "A_A") (pintype "passive"))
      (node (ref "VD24") (pin "A") (pinfunction "A_A") (pintype "passive"))
      (node (ref "VD25") (pin "A") (pinfunction "A_A") (pintype "passive"))
      (node (ref "VD26") (pin "A") (pinfunction "A_A") (pintype "passive"))
      (node (ref "VD27") (pin "A") (pinfunction "A_A") (pintype "passive"))
      (node (ref "VD28") (pin "A") (pinfunction "A_A") (pintype "passive"))
      (node (ref "VD29") (pin "A") (pinfunction "A_A") (pintype "passive"))
      (node (ref "VD3") (pin "A") (pinfunction "A_A") (pintype "passive"))
      (node (ref "VD30") (pin "A") (pinfunction "A_A") (pintype "passive"))
      (node (ref "VD31") (pin "A") (pinfunction "A_A") (pintype "passive"))
      (node (ref "VD32") (pin "A") (pinfunction "A_A") (pintype "passive"))
      (node (ref "VD33") (pin "A") (pinfunction "A_A") (pintype "passive"))
      (node (ref "VD34") (pin "A") (pinfunction "A_A") (pintype "passive"))
      (node (ref "VD35") (pin "A") (pinfunction "A_A") (pintype "passive"))
      (node (ref "VD36") (pin "A") (pinfunction "A_A") (pintype "passive"))
      (node (ref "VD37") (pin "A") (pinfunction "A_A") (pintype "passive"))
      (node (ref "VD38") (pin "A") (pinfunction "A_A") (pintype "passive"))
      (node (ref "VD39") (pin "A") (pinfunction "A_A") (pintype "passive"))
      (node (ref "VD4") (pin "A") (pinfunction "A_A") (pintype "passive"))
      (node (ref "VD40") (pin "A") (pinfunction "A_A") (pintype "passive"))
      (node (ref "VD41") (pin "A") (pinfunction "A_A") (pintype "passive"))
      (node (ref "VD42") (pin "A") (pinfunction "A_A") (pintype "passive"))
      (node (ref "VD43") (pin "A") (pinfunction "A_A") (pintype "passive"))
      (node (ref "VD44") (pin "A") (pinfunction "A_A") (pintype "passive"))
      (node (ref "VD45") (pin "A") (pinfunction "A_A") (pintype "passive"))
      (node (ref "VD46") (pin "A") (pinfunction "A_A") (pintype "passive"))
      (node (ref "VD47") (pin "A") (pinfunction "A_A") (pintype "passive"))
      (node (ref "VD48") (pin "A") (pinfunction "A_A") (pintype "passive"))
      (node (ref "VD49") (pin "A") (pinfunction "A_A") (pintype "passive"))
      (node (ref "VD5") (pin "A") (pinfunction "A_A") (pintype "passive"))
      (node (ref "VD50") (pin "A") (pinfunction "A_A") (pintype "passive"))
      (node (ref "VD51") (pin "A") (pinfunction "A_A") (pintype "passive"))
      (node (ref "VD52") (pin "A") (pinfunction "A_A") (pintype "passive"))
      (node (ref "VD53") (pin "A") (pinfunction "A_A") (pintype "passive"))
      (node (ref "VD54") (pin "A") (pinfunction "A_A") (pintype "passive"))
      (node (ref "VD55") (pin "A") (pinfunction "A_A") (pintype "passive"))
      (node (ref "VD6") (pin "A") (pinfunction "A_A") (pintype "passive"))
      (node (ref "VD7") (pin "A") (pinfunction "A_A") (pintype "passive"))
      (node (ref "VD8") (pin "A") (pinfunction "A_A") (pintype "passive"))
      (node (ref "VD9") (pin "A") (pinfunction "A_A") (pintype "passive"))
      (node (ref "VT1") (pin "E") (pinfunction "E_E") (pintype "passive"))
      (node (ref "VT10") (pin "E") (pinfunction "E_E") (pintype "passive"))
      (node (ref "VT11") (pin "E") (pinfunction "E_E") (pintype "passive"))
      (node (ref "VT12") (pin "E") (pinfunction "E_E") (pintype "passive"))
      (node (ref "VT13") (pin "E") (pinfunction "E_E") (pintype "passive"))
      (node (ref "VT14") (pin "E") (pinfunction "E_E") (pintype "passive"))
      (node (ref "VT15") (pin "E") (pinfunction "E_E") (pintype "passive"))
      (node (ref "VT16") (pin "E") (pinfunction "E_E") (pintype "passive"))
      (node (ref "VT17") (pin "E") (pinfunction "E_E") (pintype "passive"))
      (node (ref "VT18") (pin "E") (pinfunction "E_E") (pintype "passive"))
      (node (ref "VT19") (pin "E") (pinfunction "E_E") (pintype "passive"))
      (node (ref "VT2") (pin "E") (pinfunction "E_E") (pintype "passive"))
      (node (ref "VT20") (pin "E") (pinfunction "E_E") (pintype "passive"))
      (node (ref "VT21") (pin "E") (pinfunction "E_E") (pintype "passive"))
      (node (ref "VT22") (pin "E") (pinfunction "E_E") (pintype "passive"))
      (node (ref "VT23") (pin "E") (pinfunction "E_E") (pintype "passive"))
      (node (ref "VT24") (pin "E") (pinfunction "E_E") (pintype "passive"))
      (node (ref "VT25") (pin "E") (pinfunction "E_E") (pintype "passive"))
      (node (ref "VT26") (pin "E") (pinfunction "E_E") (pintype "passive"))
      (node (ref "VT27") (pin "E") (pinfunction "E_E") (pintype "passive"))
      (node (ref "VT28") (pin "E") (pinfunction "E_E") (pintype "passive"))
      (node (ref "VT29") (pin "E") (pinfunction "E_E") (pintype "passive"))
      (node (ref "VT3") (pin "E") (pinfunction "E_E") (pintype "passive"))
      (node (ref "VT30") (pin "E") (pinfunction "E_E") (pintype "passive"))
      (node (ref "VT31") (pin "E") (pinfunction "E_E") (pintype "passive"))
      (node (ref "VT32") (pin "E") (pinfunction "E_E") (pintype "passive"))
      (node (ref "VT33") (pin "E") (pinfunction "E_E") (pintype "passive"))
      (node (ref "VT34") (pin "E") (pinfunction "E_E") (pintype "passive"))
      (node (ref "VT35") (pin "E") (pinfunction "E_E") (pintype "passive"))
      (node (ref "VT36") (pin "E") (pinfunction "E_E") (pintype "passive"))
      (node (ref "VT37") (pin "E") (pinfunction "E_E") (pintype "passive"))
      (node (ref "VT38") (pin "E") (pinfunction "E_E") (pintype "passive"))
      (node (ref "VT39") (pin "E") (pinfunction "E_E") (pintype "passive"))
      (node (ref "VT4") (pin "E") (pinfunction "E_E") (pintype "passive"))
      (node (ref "VT40") (pin "E") (pinfunction "E_E") (pintype "passive"))
      (node (ref "VT41") (pin "E") (pinfunction "E_E") (pintype "passive"))
      (node (ref "VT42") (pin "E") (pinfunction "E_E") (pintype "passive"))
      (node (ref "VT43") (pin "E") (pinfunction "E_E") (pintype "passive"))
      (node (ref "VT44") (pin "E") (pinfunction "E_E") (pintype "passive"))
      (node (ref "VT45") (pin "E") (pinfunction "E_E") (pintype "passive"))
      (node (ref "VT46") (pin "E") (pinfunction "E_E") (pintype "passive"))
      (node (ref "VT47") (pin "E") (pinfunction "E_E") (pintype "passive"))
      (node (ref "VT48") (pin "E") (pinfunction "E_E") (pintype "passive"))
      (node (ref "VT49") (pin "E") (pinfunction "E_E") (pintype "passive"))
      (node (ref "VT5") (pin "E") (pinfunction "E_E") (pintype "passive"))
      (node (ref "VT50") (pin "E") (pinfunction "E_E") (pintype "passive"))
      (node (ref "VT51") (pin "E") (pinfunction "E_E") (pintype "passive"))
      (node (ref "VT52") (pin "E") (pinfunction "E_E") (pintype "passive"))
      (node (ref "VT53") (pin "E") (pinfunction "E_E") (pintype "passive"))
      (node (ref "VT54") (pin "E") (pinfunction "E_E") (pintype "passive"))
      (node (ref "VT55") (pin "E") (pinfunction "E_E") (pintype "passive"))
      (node (ref "VT6") (pin "E") (pinfunction "E_E") (pintype "passive"))
      (node (ref "VT7") (pin "E") (pinfunction "E_E") (pintype "passive"))
      (node (ref "VT8") (pin "E") (pinfunction "E_E") (pintype "passive"))
      (node (ref "VT9") (pin "E") (pinfunction "E_E") (pintype "passive"))
    )
    (net (code "59") (name "Net-(C3-Pad1)") (class "Default")
      (node (ref "C3") (pin "1") (pinfunction "1_1") (pintype "passive"))
      (node (ref "C4") (pin "1") (pinfunction "1_1") (pintype "passive"))
      (node (ref "J2") (pin "2") (pinfunction "2_2") (pintype "passive"))
    )
    (net (code "60") (name "Net-(DD1A-32KHZ)") (class "Default")
      (node (ref "DD1A") (pin "1") (pinfunction "32KHZ_1") (pintype "bidirectional"))
      (node (ref "R110") (pin "1") (pinfunction "1_1") (pintype "passive"))
    )
    (net (code "61") (name "Net-(DD1A-SCL)") (class "Default")
      (node (ref "DD1A") (pin "16") (pinfunction "SCL_16") (pintype "bidirectional"))
      (node (ref "J4") (pin "1") (pinfunction "1_1") (pintype "passive"))
    )
    (net (code "62") (name "Net-(DD1A-~{INT})") (class "Default")
      (node (ref "DD1A") (pin "3") (pinfunction "~{INT}_3") (pintype "bidirectional"))
      (node (ref "J5") (pin "2") (pinfunction "2_2") (pintype "passive"))
    )
    (net (code "63") (name "Net-(DD1A-~{RST})") (class "Default")
      (node (ref "DD1A") (pin "4") (pinfunction "~{RST}_4") (pintype "bidirectional"))
      (node (ref "R113") (pin "1") (pinfunction "1_1") (pintype "passive"))
    )
    (net (code "64") (name "Net-(DD1B-X1)") (class "Default")
      (node (ref "DD1B") (pin "1") (pinfunction "X1_1") (pintype "input"))
      (node (ref "Z1") (pin "P$2") (pinfunction "2_P$2") (pintype "passive"))
    )
    (net (code "65") (name "Net-(DD1B-X2)") (class "Default")
      (node (ref "DD1B") (pin "2") (pinfunction "X2_2") (pintype "output"))
      (node (ref "Z1") (pin "P$1") (pinfunction "1_P$1") (pintype "passive"))
    )
    (net (code "66") (name "Net-(DD2-PB6(XTAL1{slash}TOSC1))") (class "Default")
      (node (ref "C3") (pin "2") (pinfunction "2_2") (pintype "passive"))
      (node (ref "DD2") (pin "7") (pinfunction "PB6(XTAL1/TOSC1)_7") (pintype "bidirectional"))
      (node (ref "Q1") (pin "2") (pinfunction "2_2") (pintype "passive"))
    )
    (net (code "67") (name "Net-(DD2-PB7(XTAL2{slash}TOSC2))") (class "Default")
      (node (ref "C4") (pin "2") (pinfunction "2_2") (pintype "passive"))
      (node (ref "DD2") (pin "8") (pinfunction "PB7(XTAL2/TOSC2)_8") (pintype "bidirectional"))
      (node (ref "Q1") (pin "1") (pinfunction "1_1") (pintype "passive"))
    )
    (net (code "68") (name "Net-(IC1A-QH*)") (class "Default")
      (node (ref "IC1") (pin "9") (pinfunction "QH*_9") (pintype "tri_state"))
      (node (ref "IC2") (pin "14") (pinfunction "SER_14") (pintype "input"))
    )
    (net (code "69") (name "Net-(IC2A-QH*)") (class "Default")
      (node (ref "IC2") (pin "9") (pinfunction "QH*_9") (pintype "tri_state"))
      (node (ref "IC3") (pin "14") (pinfunction "SER_14") (pintype "input"))
    )
    (net (code "70") (name "Net-(IC3A-QH*)") (class "Default")
      (node (ref "IC3") (pin "9") (pinfunction "QH*_9") (pintype "tri_state"))
      (node (ref "IC4") (pin "14") (pinfunction "SER_14") (pintype "input"))
    )
    (net (code "71") (name "Net-(IC4A-QH*)") (class "Default")
      (node (ref "IC4") (pin "9") (pinfunction "QH*_9") (pintype "tri_state"))
      (node (ref "J6") (pin "1") (pinfunction "1_1") (pintype "passive"))
    )
    (net (code "72") (name "Net-(IC5A-QH*)") (class "Default")
      (node (ref "IC5") (pin "9") (pinfunction "QH*_9") (pintype "tri_state"))
      (node (ref "IC6") (pin "14") (pinfunction "SER_14") (pintype "input"))
    )
    (net (code "73") (name "Net-(IC5A-SER)") (class "Default")
      (node (ref "IC5") (pin "14") (pinfunction "SER_14") (pintype "input"))
      (node (ref "J6") (pin "2") (pinfunction "2_2") (pintype "passive"))
    )
    (net (code "74") (name "Net-(IC6A-QH*)") (class "Default")
      (node (ref "IC6") (pin "9") (pinfunction "QH*_9") (pintype "tri_state"))
      (node (ref "IC7") (pin "14") (pinfunction "SER_14") (pintype "input"))
    )
    (net (code "75") (name "Net-(ISP-Pad2)") (class "Default")
      (node (ref "ISP") (pin "2") (pinfunction "2_2") (pintype "passive"))
      (node (ref "J1") (pin "1") (pinfunction "1_1") (pintype "passive"))
    )
    (net (code "76") (name "Net-(N26-PadA)") (class "Default")
      (node (ref "N26") (pin "A") (pinfunction "A_A") (pintype "bidirectional"))
      (node (ref "R78") (pin "1") (pinfunction "1_1") (pintype "passive"))
    )
    (net (code "77") (name "Net-(R1-Pad2)") (class "Default")
      (node (ref "R1") (pin "2") (pinfunction "2_2") (pintype "passive"))
      (node (ref "VD1") (pin "C") (pinfunction "C_C") (pintype "passive"))
      (node (ref "VT1") (pin "B") (pinfunction "B_B") (pintype "passive"))
    )
    (net (code "78") (name "Net-(R2-Pad1)") (class "Default")
      (node (ref "R2") (pin "1") (pinfunction "1_1") (pintype "passive"))
      (node (ref "VT1") (pin "C") (pinfunction "C_C") (pintype "passive"))
    )
    (net (code "79") (name "Net-(R3-Pad2)") (class "Default")
      (node (ref "R3") (pin "2") (pinfunction "2_2") (pintype "passive"))
      (node (ref "VD2") (pin "C") (pinfunction "C_C") (pintype "passive"))
      (node (ref "VT2") (pin "B") (pinfunction "B_B") (pintype "passive"))
    )
    (net (code "80") (name "Net-(R4-Pad1)") (class "Default")
      (node (ref "R4") (pin "1") (pinfunction "1_1") (pintype "passive"))
      (node (ref "VT2") (pin "C") (pinfunction "C_C") (pintype "passive"))
    )
    (net (code "81") (name "Net-(R5-Pad2)") (class "Default")
      (node (ref "R5") (pin "2") (pinfunction "2_2") (pintype "passive"))
      (node (ref "VD3") (pin "C") (pinfunction "C_C") (pintype "passive"))
      (node (ref "VT3") (pin "B") (pinfunction "B_B") (pintype "passive"))
    )
    (net (code "82") (name "Net-(R6-Pad1)") (class "Default")
      (node (ref "R6") (pin "1") (pinfunction "1_1") (pintype "passive"))
      (node (ref "VT3") (pin "C") (pinfunction "C_C") (pintype "passive"))
    )
    (net (code "83") (name "Net-(R7-Pad2)") (class "Default")
      (node (ref "R7") (pin "2") (pinfunction "2_2") (pintype "passive"))
      (node (ref "VD4") (pin "C") (pinfunction "C_C") (pintype "passive"))
      (node (ref "VT4") (pin "B") (pinfunction "B_B") (pintype "passive"))
    )
    (net (code "84") (name "Net-(R8-Pad1)") (class "Default")
      (node (ref "R8") (pin "1") (pinfunction "1_1") (pintype "passive"))
      (node (ref "VT4") (pin "C") (pinfunction "C_C") (pintype "passive"))
    )
    (net (code "85") (name "Net-(R9-Pad2)") (class "Default")
      (node (ref "R9") (pin "2") (pinfunction "2_2") (pintype "passive"))
      (node (ref "VD5") (pin "C") (pinfunction "C_C") (pintype "passive"))
      (node (ref "VT5") (pin "B") (pinfunction "B_B") (pintype "passive"))
    )
    (net (code "86") (name "Net-(R10-Pad1)") (class "Default")
      (node (ref "R10") (pin "1") (pinfunction "1_1") (pintype "passive"))
      (node (ref "VT5") (pin "C") (pinfunction "C_C") (pintype "passive"))
    )
    (net (code "87") (name "Net-(R11-Pad2)") (class "Default")
      (node (ref "R11") (pin "2") (pinfunction "2_2") (pintype "passive"))
      (node (ref "VD6") (pin "C") (pinfunction "C_C") (pintype "passive"))
      (node (ref "VT6") (pin "B") (pinfunction "B_B") (pintype "passive"))
    )
    (net (code "88") (name "Net-(R12-Pad1)") (class "Default")
      (node (ref "R12") (pin "1") (pinfunction "1_1") (pintype "passive"))
      (node (ref "VT6") (pin "C") (pinfunction "C_C") (pintype "passive"))
    )
    (net (code "89") (name "Net-(R13-Pad2)") (class "Default")
      (node (ref "R13") (pin "2") (pinfunction "2_2") (pintype "passive"))
      (node (ref "VD7") (pin "C") (pinfunction "C_C") (pintype "passive"))
      (node (ref "VT7") (pin "B") (pinfunction "B_B") (pintype "passive"))
    )
    (net (code "90") (name "Net-(R14-Pad1)") (class "Default")
      (node (ref "R14") (pin "1") (pinfunction "1_1") (pintype "passive"))
      (node (ref "VT7") (pin "C") (pinfunction "C_C") (pintype "passive"))
    )
    (net (code "91") (name "Net-(R15-Pad2)") (class "Default")
      (node (ref "R15") (pin "2") (pinfunction "2_2") (pintype "passive"))
      (node (ref "VD8") (pin "C") (pinfunction "C_C") (pintype "passive"))
      (node (ref "VT8") (pin "B") (pinfunction "B_B") (pintype "passive"))
    )
    (net (code "92") (name "Net-(R16-Pad1)") (class "Default")
      (node (ref "R16") (pin "1") (pinfunction "1_1") (pintype "passive"))
      (node (ref "VT8") (pin "C") (pinfunction "C_C") (pintype "passive"))
    )
    (net (code "93") (name "Net-(R17-Pad2)") (class "Default")
      (node (ref "R17") (pin "2") (pinfunction "2_2") (pintype "passive"))
      (node (ref "VD9") (pin "C") (pinfunction "C_C") (pintype "passive"))
      (node (ref "VT9") (pin "B") (pinfunction "B_B") (pintype "passive"))
    )
    (net (code "94") (name "Net-(R18-Pad1)") (class "Default")
      (node (ref "R18") (pin "1") (pinfunction "1_1") (pintype "passive"))
      (node (ref "VT9") (pin "C") (pinfunction "C_C") (pintype "passive"))
    )
    (net (code "95") (name "Net-(R19-Pad2)") (class "Default")
      (node (ref "R19") (pin "2") (pinfunction "2_2") (pintype "passive"))
      (node (ref "VD10") (pin "C") (pinfunction "C_C") (pintype "passive"))
      (node (ref "VT10") (pin "B") (pinfunction "B_B") (pintype "passive"))
    )
    (net (code "96") (name "Net-(R20-Pad1)") (class "Default")
      (node (ref "R20") (pin "1") (pinfunction "1_1") (pintype "passive"))
      (node (ref "VT10") (pin "C") (pinfunction "C_C") (pintype "passive"))
    )
    (net (code "97") (name "Net-(R21-Pad2)") (class "Default")
      (node (ref "R21") (pin "2") (pinfunction "2_2") (pintype "passive"))
      (node (ref "VD11") (pin "C") (pinfunction "C_C") (pintype "passive"))
      (node (ref "VT11") (pin "B") (pinfunction "B_B") (pintype "passive"))
    )
    (net (code "98") (name "Net-(R22-Pad1)") (class "Default")
      (node (ref "R22") (pin "1") (pinfunction "1_1") (pintype "passive"))
      (node (ref "VT11") (pin "C") (pinfunction "C_C") (pintype "passive"))
    )
    (net (code "99") (name "Net-(R23-Pad2)") (class "Default")
      (node (ref "R23") (pin "2") (pinfunction "2_2") (pintype "passive"))
      (node (ref "VD12") (pin "C") (pinfunction "C_C") (pintype "passive"))
      (node (ref "VT12") (pin "B") (pinfunction "B_B") (pintype "passive"))
    )
    (net (code "100") (name "Net-(R24-Pad1)") (class "Default")
      (node (ref "R24") (pin "1") (pinfunction "1_1") (pintype "passive"))
      (node (ref "VT12") (pin "C") (pinfunction "C_C") (pintype "passive"))
    )
    (net (code "101") (name "Net-(R25-Pad2)") (class "Default")
      (node (ref "R25") (pin "2") (pinfunction "2_2") (pintype "passive"))
      (node (ref "VD13") (pin "C") (pinfunction "C_C") (pintype "passive"))
      (node (ref "VT13") (pin "B") (pinfunction "B_B") (pintype "passive"))
    )
    (net (code "102") (name "Net-(R26-Pad1)") (class "Default")
      (node (ref "R26") (pin "1") (pinfunction "1_1") (pintype "passive"))
      (node (ref "VT13") (pin "C") (pinfunction "C_C") (pintype "passive"))
    )
    (net (code "103") (name "Net-(R27-Pad2)") (class "Default")
      (node (ref "R27") (pin "2") (pinfunction "2_2") (pintype "passive"))
      (node (ref "VD14") (pin "C") (pinfunction "C_C") (pintype "passive"))
      (node (ref "VT14") (pin "B") (pinfunction "B_B") (pintype "passive"))
    )
    (net (code "104") (name "Net-(R28-Pad1)") (class "Default")
      (node (ref "R28") (pin "1") (pinfunction "1_1") (pintype "passive"))
      (node (ref "VT14") (pin "C") (pinfunction "C_C") (pintype "passive"))
    )
    (net (code "105") (name "Net-(R29-Pad2)") (class "Default")
      (node (ref "R29") (pin "2") (pinfunction "2_2") (pintype "passive"))
      (node (ref "VD15") (pin "C") (pinfunction "C_C") (pintype "passive"))
      (node (ref "VT15") (pin "B") (pinfunction "B_B") (pintype "passive"))
    )
    (net (code "106") (name "Net-(R30-Pad1)") (class "Default")
      (node (ref "R30") (pin "1") (pinfunction "1_1") (pintype "passive"))
      (node (ref "VT15") (pin "C") (pinfunction "C_C") (pintype "passive"))
    )
    (net (code "107") (name "Net-(R31-Pad2)") (class "Default")
      (node (ref "R31") (pin "2") (pinfunction "2_2") (pintype "passive"))
      (node (ref "VD16") (pin "C") (pinfunction "C_C") (pintype "passive"))
      (node (ref "VT16") (pin "B") (pinfunction "B_B") (pintype "passive"))
    )
    (net (code "108") (name "Net-(R32-Pad1)") (class "Default")
      (node (ref "R32") (pin "1") (pinfunction "1_1") (pintype "passive"))
      (node (ref "VT16") (pin "C") (pinfunction "C_C") (pintype "passive"))
    )
    (net (code "109") (name "Net-(R33-Pad2)") (class "Default")
      (node (ref "R33") (pin "2") (pinfunction "2_2") (pintype "passive"))
      (node (ref "VD17") (pin "C") (pinfunction "C_C") (pintype "passive"))
      (node (ref "VT17") (pin "B") (pinfunction "B_B") (pintype "passive"))
    )
    (net (code "110") (name "Net-(R34-Pad1)") (class "Default")
      (node (ref "R34") (pin "1") (pinfunction "1_1") (pintype "passive"))
      (node (ref "VT17") (pin "C") (pinfunction "C_C") (pintype "passive"))
    )
    (net (code "111") (name "Net-(R35-Pad2)") (class "Default")
      (node (ref "R35") (pin "2") (pinfunction "2_2") (pintype "passive"))
      (node (ref "VD18") (pin "C") (pinfunction "C_C") (pintype "passive"))
      (node (ref "VT18") (pin "B") (pinfunction "B_B") (pintype "passive"))
    )
    (net (code "112") (name "Net-(R36-Pad1)") (class "Default")
      (node (ref "R36") (pin "1") (pinfunction "1_1") (pintype "passive"))
      (node (ref "VT18") (pin "C") (pinfunction "C_C") (pintype "passive"))
    )
    (net (code "113") (name "Net-(R37-Pad2)") (class "Default")
      (node (ref "R37") (pin "2") (pinfunction "2_2") (pintype "passive"))
      (node (ref "VD19") (pin "C") (pinfunction "C_C") (pintype "passive"))
      (node (ref "VT19") (pin "B") (pinfunction "B_B") (pintype "passive"))
    )
    (net (code "114") (name "Net-(R38-Pad1)") (class "Default")
      (node (ref "R38") (pin "1") (pinfunction "1_1") (pintype "passive"))
      (node (ref "VT19") (pin "C") (pinfunction "C_C") (pintype "passive"))
    )
    (net (code "115") (name "Net-(R39-Pad2)") (class "Default")
      (node (ref "R39") (pin "2") (pinfunction "2_2") (pintype "passive"))
      (node (ref "VD20") (pin "C") (pinfunction "C_C") (pintype "passive"))
      (node (ref "VT20") (pin "B") (pinfunction "B_B") (pintype "passive"))
    )
    (net (code "116") (name "Net-(R40-Pad1)") (class "Default")
      (node (ref "R40") (pin "1") (pinfunction "1_1") (pintype "passive"))
      (node (ref "VT20") (pin "C") (pinfunction "C_C") (pintype "passive"))
    )
    (net (code "117") (name "Net-(R41-Pad2)") (class "Default")
      (node (ref "R41") (pin "2") (pinfunction "2_2") (pintype "passive"))
      (node (ref "VD21") (pin "C") (pinfunction "C_C") (pintype "passive"))
      (node (ref "VT21") (pin "B") (pinfunction "B_B") (pintype "passive"))
    )
    (net (code "118") (name "Net-(R42-Pad1)") (class "Default")
      (node (ref "R42") (pin "1") (pinfunction "1_1") (pintype "passive"))
      (node (ref "VT21") (pin "C") (pinfunction "C_C") (pintype "passive"))
    )
    (net (code "119") (name "Net-(R43-Pad2)") (class "Default")
      (node (ref "R43") (pin "2") (pinfunction "2_2") (pintype "passive"))
      (node (ref "VD22") (pin "C") (pinfunction "C_C") (pintype "passive"))
      (node (ref "VT22") (pin "B") (pinfunction "B_B") (pintype "passive"))
    )
    (net (code "120") (name "Net-(R44-Pad1)") (class "Default")
      (node (ref "R44") (pin "1") (pinfunction "1_1") (pintype "passive"))
      (node (ref "VT22") (pin "C") (pinfunction "C_C") (pintype "passive"))
    )
    (net (code "121") (name "Net-(R45-Pad2)") (class "Default")
      (node (ref "R45") (pin "2") (pinfunction "2_2") (pintype "passive"))
      (node (ref "VD23") (pin "C") (pinfunction "C_C") (pintype "passive"))
      (node (ref "VT23") (pin "B") (pinfunction "B_B") (pintype "passive"))
    )
    (net (code "122") (name "Net-(R46-Pad1)") (class "Default")
      (node (ref "R46") (pin "1") (pinfunction "1_1") (pintype "passive"))
      (node (ref "VT23") (pin "C") (pinfunction "C_C") (pintype "passive"))
    )
    (net (code "123") (name "Net-(R47-Pad2)") (class "Default")
      (node (ref "R47") (pin "2") (pinfunction "2_2") (pintype "passive"))
      (node (ref "VD24") (pin "C") (pinfunction "C_C") (pintype "passive"))
      (node (ref "VT24") (pin "B") (pinfunction "B_B") (pintype "passive"))
    )
    (net (code "124") (name "Net-(R48-Pad1)") (class "Default")
      (node (ref "R48") (pin "1") (pinfunction "1_1") (pintype "passive"))
      (node (ref "VT24") (pin "C") (pinfunction "C_C") (pintype "passive"))
    )
    (net (code "125") (name "Net-(R49-Pad2)") (class "Default")
      (node (ref "R49") (pin "2") (pinfunction "2_2") (pintype "passive"))
      (node (ref "VD25") (pin "C") (pinfunction "C_C") (pintype "passive"))
      (node (ref "VT25") (pin "B") (pinfunction "B_B") (pintype "passive"))
    )
    (net (code "126") (name "Net-(R50-Pad1)") (class "Default")
      (node (ref "R50") (pin "1") (pinfunction "1_1") (pintype "passive"))
      (node (ref "VT25") (pin "C") (pinfunction "C_C") (pintype "passive"))
    )
    (net (code "127") (name "Net-(R51-Pad2)") (class "Default")
      (node (ref "R51") (pin "2") (pinfunction "2_2") (pintype "passive"))
      (node (ref "VD26") (pin "C") (pinfunction "C_C") (pintype "passive"))
      (node (ref "VT26") (pin "B") (pinfunction "B_B") (pintype "passive"))
    )
    (net (code "128") (name "Net-(R52-Pad1)") (class "Default")
      (node (ref "R52") (pin "1") (pinfunction "1_1") (pintype "passive"))
      (node (ref "VT26") (pin "C") (pinfunction "C_C") (pintype "passive"))
    )
    (net (code "129") (name "Net-(R53-Pad2)") (class "Default")
      (node (ref "R53") (pin "2") (pinfunction "2_2") (pintype "passive"))
      (node (ref "VD27") (pin "C") (pinfunction "C_C") (pintype "passive"))
      (node (ref "VT27") (pin "B") (pinfunction "B_B") (pintype "passive"))
    )
    (net (code "130") (name "Net-(R54-Pad1)") (class "Default")
      (node (ref "R54") (pin "1") (pinfunction "1_1") (pintype "passive"))
      (node (ref "VT27") (pin "C") (pinfunction "C_C") (pintype "passive"))
    )
    (net (code "131") (name "Net-(R55-Pad2)") (class "Default")
      (node (ref "R55") (pin "2") (pinfunction "2_2") (pintype "passive"))
      (node (ref "VD28") (pin "C") (pinfunction "C_C") (pintype "passive"))
      (node (ref "VT28") (pin "B") (pinfunction "B_B") (pintype "passive"))
    )
    (net (code "132") (name "Net-(R56-Pad1)") (class "Default")
      (node (ref "R56") (pin "1") (pinfunction "1_1") (pintype "passive"))
      (node (ref "VT28") (pin "C") (pinfunction "C_C") (pintype "passive"))
    )
    (net (code "133") (name "Net-(R57-Pad2)") (class "Default")
      (node (ref "R57") (pin "2") (pinfunction "2_2") (pintype "passive"))
      (node (ref "VD29") (pin "C") (pinfunction "C_C") (pintype "passive"))
      (node (ref "VT29") (pin "B") (pinfunction "B_B") (pintype "passive"))
    )
    (net (code "134") (name "Net-(R58-Pad1)") (class "Default")
      (node (ref "R58") (pin "1") (pinfunction "1_1") (pintype "passive"))
      (node (ref "VT29") (pin "C") (pinfunction "C_C") (pintype "passive"))
    )
    (net (code "135") (name "Net-(R59-Pad2)") (class "Default")
      (node (ref "R59") (pin "2") (pinfunction "2_2") (pintype "passive"))
      (node (ref "VD30") (pin "C") (pinfunction "C_C") (pintype "passive"))
      (node (ref "VT30") (pin "B") (pinfunction "B_B") (pintype "passive"))
    )
    (net (code "136") (name "Net-(R60-Pad1)") (class "Default")
      (node (ref "R60") (pin "1") (pinfunction "1_1") (pintype "passive"))
      (node (ref "VT30") (pin "C") (pinfunction "C_C") (pintype "passive"))
    )
    (net (code "137") (name "Net-(R61-Pad2)") (class "Default")
      (node (ref "R61") (pin "2") (pinfunction "2_2") (pintype "passive"))
      (node (ref "VD31") (pin "C") (pinfunction "C_C") (pintype "passive"))
      (node (ref "VT31") (pin "B") (pinfunction "B_B") (pintype "passive"))
    )
    (net (code "138") (name "Net-(R62-Pad1)") (class "Default")
      (node (ref "R62") (pin "1") (pinfunction "1_1") (pintype "passive"))
      (node (ref "VT31") (pin "C") (pinfunction "C_C") (pintype "passive"))
    )
    (net (code "139") (name "Net-(R63-Pad2)") (class "Default")
      (node (ref "R63") (pin "2") (pinfunction "2_2") (pintype "passive"))
      (node (ref "VD32") (pin "C") (pinfunction "C_C") (pintype "passive"))
      (node (ref "VT32") (pin "B") (pinfunction "B_B") (pintype "passive"))
    )
    (net (code "140") (name "Net-(R64-Pad1)") (class "Default")
      (node (ref "R64") (pin "1") (pinfunction "1_1") (pintype "passive"))
      (node (ref "VT32") (pin "C") (pinfunction "C_C") (pintype "passive"))
    )
    (net (code "141") (name "Net-(R65-Pad2)") (class "Default")
      (node (ref "R65") (pin "2") (pinfunction "2_2") (pintype "passive"))
      (node (ref "VD33") (pin "C") (pinfunction "C_C") (pintype "passive"))
      (node (ref "VT33") (pin "B") (pinfunction "B_B") (pintype "passive"))
    )
    (net (code "142") (name "Net-(R66-Pad1)") (class "Default")
      (node (ref "R66") (pin "1") (pinfunction "1_1") (pintype "passive"))
      (node (ref "VT33") (pin "C") (pinfunction "C_C") (pintype "passive"))
    )
    (net (code "143") (name "Net-(R67-Pad2)") (class "Default")
      (node (ref "R67") (pin "2") (pinfunction "2_2") (pintype "passive"))
      (node (ref "VD34") (pin "C") (pinfunction "C_C") (pintype "passive"))
      (node (ref "VT34") (pin "B") (pinfunction "B_B") (pintype "passive"))
    )
    (net (code "144") (name "Net-(R68-Pad1)") (class "Default")
      (node (ref "R68") (pin "1") (pinfunction "1_1") (pintype "passive"))
      (node (ref "VT34") (pin "C") (pinfunction "C_C") (pintype "passive"))
    )
    (net (code "145") (name "Net-(R69-Pad2)") (class "Default")
      (node (ref "R69") (pin "2") (pinfunction "2_2") (pintype "passive"))
      (node (ref "VD35") (pin "C") (pinfunction "C_C") (pintype "passive"))
      (node (ref "VT35") (pin "B") (pinfunction "B_B") (pintype "passive"))
    )
    (net (code "146") (name "Net-(R70-Pad1)") (class "Default")
      (node (ref "R70") (pin "1") (pinfunction "1_1") (pintype "passive"))
      (node (ref "VT35") (pin "C") (pinfunction "C_C") (pintype "passive"))
    )
    (net (code "147") (name "Net-(R71-Pad2)") (class "Default")
      (node (ref "R71") (pin "2") (pinfunction "2_2") (pintype "passive"))
      (node (ref "VD36") (pin "C") (pinfunction "C_C") (pintype "passive"))
      (node (ref "VT36") (pin "B") (pinfunction "B_B") (pintype "passive"))
    )
    (net (code "148") (name "Net-(R72-Pad1)") (class "Default")
      (node (ref "R72") (pin "1") (pinfunction "1_1") (pintype "passive"))
      (node (ref "VT36") (pin "C") (pinfunction "C_C") (pintype "passive"))
    )
    (net (code "149") (name "Net-(R73-Pad2)") (class "Default")
      (node (ref "R73") (pin "2") (pinfunction "2_2") (pintype "passive"))
      (node (ref "VD37") (pin "C") (pinfunction "C_C") (pintype "passive"))
      (node (ref "VT37") (pin "B") (pinfunction "B_B") (pintype "passive"))
    )
    (net (code "150") (name "Net-(R74-Pad1)") (class "Default")
      (node (ref "R74") (pin "1") (pinfunction "1_1") (pintype "passive"))
      (node (ref "VT37") (pin "C") (pinfunction "C_C") (pintype "passive"))
    )
    (net (code "151") (name "Net-(R75-Pad2)") (class "Default")
      (node (ref "R75") (pin "2") (pinfunction "2_2") (pintype "passive"))
      (node (ref "VD38") (pin "C") (pinfunction "C_C") (pintype "passive"))
      (node (ref "VT38") (pin "B") (pinfunction "B_B") (pintype "passive"))
    )
    (net (code "152") (name "Net-(R76-Pad1)") (class "Default")
      (node (ref "R76") (pin "1") (pinfunction "1_1") (pintype "passive"))
      (node (ref "VT38") (pin "C") (pinfunction "C_C") (pintype "passive"))
    )
    (net (code "153") (name "Net-(R77-Pad2)") (class "Default")
      (node (ref "R77") (pin "2") (pinfunction "2_2") (pintype "passive"))
      (node (ref "VD39") (pin "C") (pinfunction "C_C") (pintype "passive"))
      (node (ref "VT39") (pin "B") (pinfunction "B_B") (pintype "passive"))
    )
    (net (code "154") (name "Net-(R79-Pad2)") (class "Default")
      (node (ref "R79") (pin "2") (pinfunction "2_2") (pintype "passive"))
      (node (ref "VD40") (pin "C") (pinfunction "C_C") (pintype "passive"))
      (node (ref "VT40") (pin "B") (pinfunction "B_B") (pintype "passive"))
    )
    (net (code "155") (name "Net-(R80-Pad1)") (class "Default")
      (node (ref "R80") (pin "1") (pinfunction "1_1") (pintype "passive"))
      (node (ref "VT40") (pin "C") (pinfunction "C_C") (pintype "passive"))
    )
    (net (code "156") (name "Net-(R81-Pad2)") (class "Default")
      (node (ref "R81") (pin "2") (pinfunction "2_2") (pintype "passive"))
      (node (ref "VD41") (pin "C") (pinfunction "C_C") (pintype "passive"))
      (node (ref "VT41") (pin "B") (pinfunction "B_B") (pintype "passive"))
    )
    (net (code "157") (name "Net-(R82-Pad1)") (class "Default")
      (node (ref "R82") (pin "1") (pinfunction "1_1") (pintype "passive"))
      (node (ref "VT41") (pin "C") (pinfunction "C_C") (pintype "passive"))
    )
    (net (code "158") (name "Net-(R83-Pad2)") (class "Default")
      (node (ref "R83") (pin "2") (pinfunction "2_2") (pintype "passive"))
      (node (ref "VD42") (pin "C") (pinfunction "C_C") (pintype "passive"))
      (node (ref "VT42") (pin "B") (pinfunction "B_B") (pintype "passive"))
    )
    (net (code "159") (name "Net-(R84-Pad1)") (class "Default")
      (node (ref "R84") (pin "1") (pinfunction "1_1") (pintype "passive"))
      (node (ref "VT42") (pin "C") (pinfunction "C_C") (pintype "passive"))
    )
    (net (code "160") (name "Net-(R85-Pad2)") (class "Default")
      (node (ref "R85") (pin "2") (pinfunction "2_2") (pintype "passive"))
      (node (ref "VD43") (pin "C") (pinfunction "C_C") (pintype "passive"))
      (node (ref "VT43") (pin "B") (pinfunction "B_B") (pintype "passive"))
    )
    (net (code "161") (name "Net-(R86-Pad1)") (class "Default")
      (node (ref "R86") (pin "1") (pinfunction "1_1") (pintype "passive"))
      (node (ref "VT43") (pin "C") (pinfunction "C_C") (pintype "passive"))
    )
    (net (code "162") (name "Net-(R87-Pad2)") (class "Default")
      (node (ref "R87") (pin "2") (pinfunction "2_2") (pintype "passive"))
      (node (ref "VD44") (pin "C") (pinfunction "C_C") (pintype "passive"))
      (node (ref "VT44") (pin "B") (pinfunction "B_B") (pintype "passive"))
    )
    (net (code "163") (name "Net-(R88-Pad1)") (class "Default")
      (node (ref "R88") (pin "1") (pinfunction "1_1") (pintype "passive"))
      (node (ref "VT44") (pin "C") (pinfunction "C_C") (pintype "passive"))
    )
    (net (code "164") (name "Net-(R89-Pad2)") (class "Default")
      (node (ref "R89") (pin "2") (pinfunction "2_2") (pintype "passive"))
      (node (ref "VD45") (pin "C") (pinfunction "C_C") (pintype "passive"))
      (node (ref "VT45") (pin "B") (pinfunction "B_B") (pintype "passive"))
    )
    (net (code "165") (name "Net-(R90-Pad1)") (class "Default")
      (node (ref "R90") (pin "1") (pinfunction "1_1") (pintype "passive"))
      (node (ref "VT45") (pin "C") (pinfunction "C_C") (pintype "passive"))
    )
    (net (code "166") (name "Net-(R91-Pad2)") (class "Default")
      (node (ref "R91") (pin "2") (pinfunction "2_2") (pintype "passive"))
      (node (ref "VD46") (pin "C") (pinfunction "C_C") (pintype "passive"))
      (node (ref "VT46") (pin "B") (pinfunction "B_B") (pintype "passive"))
    )
    (net (code "167") (name "Net-(R92-Pad1)") (class "Default")
      (node (ref "R92") (pin "1") (pinfunction "1_1") (pintype "passive"))
      (node (ref "VT46") (pin "C") (pinfunction "C_C") (pintype "passive"))
    )
    (net (code "168") (name "Net-(R93-Pad2)") (class "Default")
      (node (ref "R93") (pin "2") (pinfunction "2_2") (pintype "passive"))
      (node (ref "VD47") (pin "C") (pinfunction "C_C") (pintype "passive"))
      (node (ref "VT47") (pin "B") (pinfunction "B_B") (pintype "passive"))
    )
    (net (code "169") (name "Net-(R94-Pad1)") (class "Default")
      (node (ref "R94") (pin "1") (pinfunction "1_1") (pintype "passive"))
      (node (ref "VT47") (pin "C") (pinfunction "C_C") (pintype "passive"))
    )
    (net (code "170") (name "Net-(R95-Pad2)") (class "Default")
      (node (ref "R95") (pin "2") (pinfunction "2_2") (pintype "passive"))
      (node (ref "VD48") (pin "C") (pinfunction "C_C") (pintype "passive"))
      (node (ref "VT48") (pin "B") (pinfunction "B_B") (pintype "passive"))
    )
    (net (code "171") (name "Net-(R96-Pad1)") (class "Default")
      (node (ref "R96") (pin "1") (pinfunction "1_1") (pintype "passive"))
      (node (ref "VT48") (pin "C") (pinfunction "C_C") (pintype "passive"))
    )
    (net (code "172") (name "Net-(R97-Pad2)") (class "Default")
      (node (ref "R97") (pin "2") (pinfunction "2_2") (pintype "passive"))
      (node (ref "VD49") (pin "C") (pinfunction "C_C") (pintype "passive"))
      (node (ref "VT49") (pin "B") (pinfunction "B_B") (pintype "passive"))
    )
    (net (code "173") (name "Net-(R98-Pad1)") (class "Default")
      (node (ref "R98") (pin "1") (pinfunction "1_1") (pintype "passive"))
      (node (ref "VT49") (pin "C") (pinfunction "C_C") (pintype "passive"))
    )
    (net (code "174") (name "Net-(R99-Pad2)") (class "Default")
      (node (ref "R99") (pin "2") (pinfunction "2_2") (pintype "passive"))
      (node (ref "VD50") (pin "C") (pinfunction "C_C") (pintype "passive"))
      (node (ref "VT50") (pin "B") (pinfunction "B_B") (pintype "passive"))
    )
    (net (code "175") (name "Net-(R100-Pad1)") (class "Default")
      (node (ref "R100") (pin "1") (pinfunction "1_1") (pintype "passive"))
      (node (ref "VT50") (pin "C") (pinfunction "C_C") (pintype "passive"))
    )
    (net (code "176") (name "Net-(R101-Pad2)") (class "Default")
      (node (ref "R101") (pin "2") (pinfunction "2_2") (pintype "passive"))
      (node (ref "VD51") (pin "C") (pinfunction "C_C") (pintype "passive"))
      (node (ref "VT51") (pin "B") (pinfunction "B_B") (pintype "passive"))
    )
    (net (code "177") (name "Net-(R102-Pad1)") (class "Default")
      (node (ref "R102") (pin "1") (pinfunction "1_1") (pintype "passive"))
      (node (ref "VT51") (pin "C") (pinfunction "C_C") (pintype "passive"))
    )
    (net (code "178") (name "Net-(R103-Pad2)") (class "Default")
      (node (ref "R103") (pin "2") (pinfunction "2_2") (pintype "passive"))
      (node (ref "VD52") (pin "C") (pinfunction "C_C") (pintype "passive"))
      (node (ref "VT52") (pin "B") (pinfunction "B_B") (pintype "passive"))
    )
    (net (code "179") (name "Net-(R104-Pad1)") (class "Default")
      (node (ref "R104") (pin "1") (pinfunction "1_1") (pintype "passive"))
      (node (ref "VT52") (pin "C") (pinfunction "C_C") (pintype "passive"))
    )
    (net (code "180") (name "Net-(R105-Pad2)") (class "Default")
      (node (ref "R105") (pin "2") (pinfunction "2_2") (pintype "passive"))
      (node (ref "VD54") (pin "C") (pinfunction "C_C") (pintype "passive"))
      (node (ref "VT54") (pin "B") (pinfunction "B_B") (pintype "passive"))
    )
    (net (code "181") (name "Net-(R111-Pad2)") (class "Default")
      (node (ref "R111") (pin "2") (pinfunction "2_2") (pintype "passive"))
      (node (ref "VD53") (pin "C") (pinfunction "C_C") (pintype "passive"))
      (node (ref "VT53") (pin "B") (pinfunction "B_B") (pintype "passive"))
    )
    (net (code "182") (name "Net-(R112-Pad1)") (class "Default")
      (node (ref "R112") (pin "1") (pinfunction "1_1") (pintype "passive"))
      (node (ref "VT53") (pin "C") (pinfunction "C_C") (pintype "passive"))
    )
    (net (code "183") (name "Net-(R114-Pad1)") (class "Default")
      (node (ref "R114") (pin "1") (pinfunction "1_1") (pintype "passive"))
      (node (ref "VT54") (pin "C") (pinfunction "C_C") (pintype "passive"))
    )
    (net (code "184") (name "Net-(R115-Pad2)") (class "Default")
      (node (ref "R115") (pin "2") (pinfunction "2_2") (pintype "passive"))
      (node (ref "VD55") (pin "C") (pinfunction "C_C") (pintype "passive"))
      (node (ref "VT55") (pin "B") (pinfunction "B_B") (pintype "passive"))
    )
    (net (code "185") (name "Net-(R116-Pad1)") (class "Default")
      (node (ref "R116") (pin "1") (pinfunction "1_1") (pintype "passive"))
      (node (ref "VT55") (pin "C") (pinfunction "C_C") (pintype "passive"))
    )
    (net (code "186") (name "RA1") (class "Default")
      (node (ref "IC1") (pin "15") (pinfunction "QA_15") (pintype "tri_state"))
      (node (ref "R1") (pin "1") (pinfunction "1_1") (pintype "passive"))
    )
    (net (code "187") (name "RA2") (class "Default")
      (node (ref "IC1") (pin "1") (pinfunction "QB_1") (pintype "tri_state"))
      (node (ref "R3") (pin "1") (pinfunction "1_1") (pintype "passive"))
    )
    (net (code "188") (name "RA3") (class "Default")
      (node (ref "IC1") (pin "2") (pinfunction "QC_2") (pintype "tri_state"))
      (node (ref "R5") (pin "1") (pinfunction "1_1") (pintype "passive"))
    )
    (net (code "189") (name "RA4") (class "Default")
      (node (ref "IC1") (pin "3") (pinfunction "QD_3") (pintype "tri_state"))
      (node (ref "R7") (pin "1") (pinfunction "1_1") (pintype "passive"))
    )
    (net (code "190") (name "RA5") (class "Default")
      (node (ref "IC1") (pin "4") (pinfunction "QE_4") (pintype "tri_state"))
      (node (ref "R9") (pin "1") (pinfunction "1_1") (pintype "passive"))
    )
    (net (code "191") (name "RA6") (class "Default")
      (node (ref "IC1") (pin "5") (pinfunction "QF_5") (pintype "tri_state"))
      (node (ref "R11") (pin "1") (pinfunction "1_1") (pintype "passive"))
    )
    (net (code "192") (name "RA7") (class "Default")
      (node (ref "IC1") (pin "6") (pinfunction "QG_6") (pintype "tri_state"))
      (node (ref "R13") (pin "1") (pinfunction "1_1") (pintype "passive"))
    )
    (net (code "193") (name "RA8") (class "Default")
      (node (ref "IC1") (pin "7") (pinfunction "QH_7") (pintype "tri_state"))
      (node (ref "R15") (pin "1") (pinfunction "1_1") (pintype "passive"))
    )
    (net (code "194") (name "RA9") (class "Default")
      (node (ref "IC2") (pin "15") (pinfunction "QA_15") (pintype "tri_state"))
      (node (ref "R17") (pin "1") (pinfunction "1_1") (pintype "passive"))
    )
    (net (code "195") (name "RA10") (class "Default")
      (node (ref "IC2") (pin "1") (pinfunction "QB_1") (pintype "tri_state"))
      (node (ref "R19") (pin "1") (pinfunction "1_1") (pintype "passive"))
    )
    (net (code "196") (name "RA11") (class "Default")
      (node (ref "IC2") (pin "2") (pinfunction "QC_2") (pintype "tri_state"))
      (node (ref "R21") (pin "1") (pinfunction "1_1") (pintype "passive"))
    )
    (net (code "197") (name "RA12") (class "Default")
      (node (ref "IC2") (pin "3") (pinfunction "QD_3") (pintype "tri_state"))
      (node (ref "R23") (pin "1") (pinfunction "1_1") (pintype "passive"))
    )
    (net (code "198") (name "RA13") (class "Default")
      (node (ref "IC2") (pin "4") (pinfunction "QE_4") (pintype "tri_state"))
      (node (ref "R25") (pin "1") (pinfunction "1_1") (pintype "passive"))
    )
    (net (code "199") (name "RB1") (class "Default")
      (node (ref "IC2") (pin "5") (pinfunction "QF_5") (pintype "tri_state"))
      (node (ref "R27") (pin "1") (pinfunction "1_1") (pintype "passive"))
    )
    (net (code "200") (name "RB2") (class "Default")
      (node (ref "IC2") (pin "6") (pinfunction "QG_6") (pintype "tri_state"))
      (node (ref "R29") (pin "1") (pinfunction "1_1") (pintype "passive"))
    )
    (net (code "201") (name "RB3") (class "Default")
      (node (ref "IC2") (pin "7") (pinfunction "QH_7") (pintype "tri_state"))
      (node (ref "R31") (pin "1") (pinfunction "1_1") (pintype "passive"))
    )
    (net (code "202") (name "RB4") (class "Default")
      (node (ref "IC3") (pin "15") (pinfunction "QA_15") (pintype "tri_state"))
      (node (ref "R33") (pin "1") (pinfunction "1_1") (pintype "passive"))
    )
    (net (code "203") (name "RB5") (class "Default")
      (node (ref "IC3") (pin "1") (pinfunction "QB_1") (pintype "tri_state"))
      (node (ref "R35") (pin "1") (pinfunction "1_1") (pintype "passive"))
    )
    (net (code "204") (name "RB6") (class "Default")
      (node (ref "IC3") (pin "2") (pinfunction "QC_2") (pintype "tri_state"))
      (node (ref "R37") (pin "1") (pinfunction "1_1") (pintype "passive"))
    )
    (net (code "205") (name "RB7") (class "Default")
      (node (ref "IC3") (pin "3") (pinfunction "QD_3") (pintype "tri_state"))
      (node (ref "R39") (pin "1") (pinfunction "1_1") (pintype "passive"))
    )
    (net (code "206") (name "RB8") (class "Default")
      (node (ref "IC3") (pin "4") (pinfunction "QE_4") (pintype "tri_state"))
      (node (ref "R41") (pin "1") (pinfunction "1_1") (pintype "passive"))
    )
    (net (code "207") (name "RB9") (class "Default")
      (node (ref "IC3") (pin "5") (pinfunction "QF_5") (pintype "tri_state"))
      (node (ref "R43") (pin "1") (pinfunction "1_1") (pintype "passive"))
    )
    (net (code "208") (name "RB10") (class "Default")
      (node (ref "IC3") (pin "6") (pinfunction "QG_6") (pintype "tri_state"))
      (node (ref "R45") (pin "1") (pinfunction "1_1") (pintype "passive"))
    )
    (net (code "209") (name "RB11") (class "Default")
      (node (ref "IC3") (pin "7") (pinfunction "QH_7") (pintype "tri_state"))
      (node (ref "R47") (pin "1") (pinfunction "1_1") (pintype "passive"))
    )
    (net (code "210") (name "RB12") (class "Default")
      (node (ref "IC4") (pin "15") (pinfunction "QA_15") (pintype "tri_state"))
      (node (ref "R115") (pin "1") (pinfunction "1_1") (pintype "passive"))
      (node (ref "R49") (pin "1") (pinfunction "1_1") (pintype "passive"))
    )
    (net (code "211") (name "RB13") (class "Default")
      (node (ref "IC4") (pin "1") (pinfunction "QB_1") (pintype "tri_state"))
      (node (ref "R51") (pin "1") (pinfunction "1_1") (pintype "passive"))
    )
    (net (code "212") (name "RC1") (class "Default")
      (node (ref "IC4") (pin "2") (pinfunction "QC_2") (pintype "tri_state"))
      (node (ref "R53") (pin "1") (pinfunction "1_1") (pintype "passive"))
    )
    (net (code "213") (name "RC2") (class "Default")
      (node (ref "IC4") (pin "3") (pinfunction "QD_3") (pintype "tri_state"))
      (node (ref "R55") (pin "1") (pinfunction "1_1") (pintype "passive"))
    )
    (net (code "214") (name "RC3") (class "Default")
      (node (ref "IC4") (pin "4") (pinfunction "QE_4") (pintype "tri_state"))
      (node (ref "R57") (pin "1") (pinfunction "1_1") (pintype "passive"))
    )
    (net (code "215") (name "RC4") (class "Default")
      (node (ref "IC4") (pin "5") (pinfunction "QF_5") (pintype "tri_state"))
      (node (ref "R59") (pin "1") (pinfunction "1_1") (pintype "passive"))
    )
    (net (code "216") (name "RC5") (class "Default")
      (node (ref "IC4") (pin "6") (pinfunction "QG_6") (pintype "tri_state"))
      (node (ref "R61") (pin "1") (pinfunction "1_1") (pintype "passive"))
    )
    (net (code "217") (name "RC6") (class "Default")
      (node (ref "IC4") (pin "7") (pinfunction "QH_7") (pintype "tri_state"))
      (node (ref "R63") (pin "1") (pinfunction "1_1") (pintype "passive"))
    )
    (net (code "218") (name "RC7") (class "Default")
      (node (ref "IC5") (pin "15") (pinfunction "QA_15") (pintype "tri_state"))
      (node (ref "R65") (pin "1") (pinfunction "1_1") (pintype "passive"))
    )
    (net (code "219") (name "RC8") (class "Default")
      (node (ref "IC5") (pin "1") (pinfunction "QB_1") (pintype "tri_state"))
      (node (ref "R67") (pin "1") (pinfunction "1_1") (pintype "passive"))
    )
    (net (code "220") (name "RC9") (class "Default")
      (node (ref "IC5") (pin "2") (pinfunction "QC_2") (pintype "tri_state"))
      (node (ref "R69") (pin "1") (pinfunction "1_1") (pintype "passive"))
    )
    (net (code "221") (name "RC10") (class "Default")
      (node (ref "IC5") (pin "3") (pinfunction "QD_3") (pintype "tri_state"))
      (node (ref "R71") (pin "1") (pinfunction "1_1") (pintype "passive"))
    )
    (net (code "222") (name "RC11") (class "Default")
      (node (ref "IC5") (pin "4") (pinfunction "QE_4") (pintype "tri_state"))
      (node (ref "R73") (pin "1") (pinfunction "1_1") (pintype "passive"))
    )
    (net (code "223") (name "RC12") (class "Default")
      (node (ref "IC5") (pin "5") (pinfunction "QF_5") (pintype "tri_state"))
      (node (ref "R75") (pin "1") (pinfunction "1_1") (pintype "passive"))
    )
    (net (code "224") (name "RC13") (class "Default")
      (node (ref "IC5") (pin "6") (pinfunction "QG_6") (pintype "tri_state"))
      (node (ref "R77") (pin "1") (pinfunction "1_1") (pintype "passive"))
    )
    (net (code "225") (name "RCLOCK_MISO_D12") (class "Default")
      (node (ref "DD2") (pin "16") (pinfunction "PB4(MISO)_16") (pintype "bidirectional"))
      (node (ref "IC1") (pin "11") (pinfunction "SCK_11") (pintype "input"))
      (node (ref "IC2") (pin "11") (pinfunction "SCK_11") (pintype "input"))
      (node (ref "IC3") (pin "11") (pinfunction "SCK_11") (pintype "input"))
      (node (ref "IC4") (pin "11") (pinfunction "SCK_11") (pintype "input"))
      (node (ref "IC5") (pin "11") (pinfunction "SCK_11") (pintype "input"))
      (node (ref "IC6") (pin "11") (pinfunction "SCK_11") (pintype "input"))
      (node (ref "IC7") (pin "11") (pinfunction "SCK_11") (pintype "input"))
      (node (ref "ISP") (pin "1") (pinfunction "1_1") (pintype "passive"))
    )
    (net (code "226") (name "RD1") (class "Default")
      (node (ref "IC5") (pin "7") (pinfunction "QH_7") (pintype "tri_state"))
      (node (ref "R79") (pin "1") (pinfunction "1_1") (pintype "passive"))
    )
    (net (code "227") (name "RD2") (class "Default")
      (node (ref "IC6") (pin "15") (pinfunction "QA_15") (pintype "tri_state"))
      (node (ref "R81") (pin "1") (pinfunction "1_1") (pintype "passive"))
    )
    (net (code "228") (name "RD3") (class "Default")
      (node (ref "IC6") (pin "1") (pinfunction "QB_1") (pintype "tri_state"))
      (node (ref "R83") (pin "1") (pinfunction "1_1") (pintype "passive"))
    )
    (net (code "229") (name "RD4") (class "Default")
      (node (ref "IC6") (pin "2") (pinfunction "QC_2") (pintype "tri_state"))
      (node (ref "R85") (pin "1") (pinfunction "1_1") (pintype "passive"))
    )
    (net (code "230") (name "RD5") (class "Default")
      (node (ref "IC6") (pin "3") (pinfunction "QD_3") (pintype "tri_state"))
      (node (ref "R87") (pin "1") (pinfunction "1_1") (pintype "passive"))
    )
    (net (code "231") (name "RD6") (class "Default")
      (node (ref "IC6") (pin "4") (pinfunction "QE_4") (pintype "tri_state"))
      (node (ref "R89") (pin "1") (pinfunction "1_1") (pintype "passive"))
    )
    (net (code "232") (name "RD7") (class "Default")
      (node (ref "IC6") (pin "5") (pinfunction "QF_5") (pintype "tri_state"))
      (node (ref "R91") (pin "1") (pinfunction "1_1") (pintype "passive"))
    )
    (net (code "233") (name "RD8") (class "Default")
      (node (ref "IC6") (pin "6") (pinfunction "QG_6") (pintype "tri_state"))
      (node (ref "R93") (pin "1") (pinfunction "1_1") (pintype "passive"))
    )
    (net (code "234") (name "RD9") (class "Default")
      (node (ref "IC6") (pin "7") (pinfunction "QH_7") (pintype "tri_state"))
      (node (ref "R95") (pin "1") (pinfunction "1_1") (pintype "passive"))
    )
    (net (code "235") (name "RD10") (class "Default")
      (node (ref "IC7") (pin "15") (pinfunction "QA_15") (pintype "tri_state"))
      (node (ref "R97") (pin "1") (pinfunction "1_1") (pintype "passive"))
    )
    (net (code "236") (name "RD11") (class "Default")
      (node (ref "IC7") (pin "1") (pinfunction "QB_1") (pintype "tri_state"))
      (node (ref "R99") (pin "1") (pinfunction "1_1") (pintype "passive"))
    )
    (net (code "237") (name "RD12") (class "Default")
      (node (ref "IC7") (pin "2") (pinfunction "QC_2") (pintype "tri_state"))
      (node (ref "R101") (pin "1") (pinfunction "1_1") (pintype "passive"))
    )
    (net (code "238") (name "RD13") (class "Default")
      (node (ref "IC7") (pin "3") (pinfunction "QD_3") (pintype "tri_state"))
      (node (ref "R103") (pin "1") (pinfunction "1_1") (pintype "passive"))
    )
    (net (code "239") (name "RDATA_MOSI_D11") (class "Default")
      (node (ref "DD2") (pin "15") (pinfunction "PB3(MOSI/OC2)_15") (pintype "bidirectional"))
      (node (ref "IC1") (pin "14") (pinfunction "SER_14") (pintype "input"))
      (node (ref "ISP") (pin "4") (pinfunction "4_4") (pintype "passive"))
    )
    (net (code "240") (name "RE1") (class "Default")
      (node (ref "R111") (pin "1") (pinfunction "1_1") (pintype "passive"))
      (node (ref "RE1") (pin "1") (pinfunction "1_1") (pintype "passive"))
    )
    (net (code "241") (name "RE2") (class "Default")
      (node (ref "R105") (pin "1") (pinfunction "1_1") (pintype "passive"))
      (node (ref "RE2") (pin "1") (pinfunction "1_1") (pintype "passive"))
    )
    (net (code "242") (name "RESET") (class "Default")
      (node (ref "DD2") (pin "29") (pinfunction "PC6(/RESET)_29") (pintype "bidirectional"))
      (node (ref "ISP") (pin "5") (pinfunction "5_5") (pintype "passive"))
      (node (ref "R109") (pin "1") (pinfunction "1_1") (pintype "passive"))
    )
    (net (code "243") (name "RLATCH_D10") (class "Default")
      (node (ref "DD2") (pin "14") (pinfunction "PB2(SS/OC1B)_14") (pintype "bidirectional"))
      (node (ref "IC1") (pin "12") (pinfunction "RCK_12") (pintype "input"))
      (node (ref "IC2") (pin "12") (pinfunction "RCK_12") (pintype "input"))
      (node (ref "IC3") (pin "12") (pinfunction "RCK_12") (pintype "input"))
      (node (ref "IC4") (pin "12") (pinfunction "RCK_12") (pintype "input"))
      (node (ref "IC5") (pin "12") (pinfunction "RCK_12") (pintype "input"))
      (node (ref "IC6") (pin "12") (pinfunction "RCK_12") (pintype "input"))
      (node (ref "IC7") (pin "12") (pinfunction "RCK_12") (pintype "input"))
    )
    (net (code "244") (name "SCK") (class "Default")
      (node (ref "DD2") (pin "17") (pinfunction "PB5(SCK)_17") (pintype "bidirectional"))
      (node (ref "ISP") (pin "3") (pinfunction "3_3") (pintype "passive"))
    )
    (net (code "245") (name "SCL") (class "Default")
      (node (ref "DD1B") (pin "6") (pinfunction "SCL_6") (pintype "input"))
      (node (ref "DD2") (pin "28") (pinfunction "PC5(ADC5/SCL)_28") (pintype "bidirectional"))
      (node (ref "J4") (pin "2") (pinfunction "2_2") (pintype "passive"))
      (node (ref "R108") (pin "1") (pinfunction "1_1") (pintype "passive"))
    )
    (net (code "246") (name "SDA") (class "Default")
      (node (ref "DD1A") (pin "15") (pinfunction "SDA_15") (pintype "bidirectional"))
      (node (ref "DD1B") (pin "5") (pinfunction "SDA_5") (pintype "bidirectional"))
      (node (ref "DD2") (pin "27") (pinfunction "PC4(ADC4/SDA)_27") (pintype "bidirectional"))
      (node (ref "R107") (pin "1") (pinfunction "1_1") (pintype "passive"))
    )
    (net (code "247") (name "SEQ") (class "Default")
      (node (ref "DD1B") (pin "7") (pinfunction "SQW_7") (pintype "open_collector"))
      (node (ref "DD2") (pin "32") (pinfunction "PD2(INT0)_32") (pintype "bidirectional"))
      (node (ref "J5") (pin "1") (pinfunction "1_1") (pintype "passive"))
      (node (ref "R106") (pin "1") (pinfunction "1_1") (pintype "passive"))
    )
    (net (code "248") (name "VBAT") (class "Default")
      (node (ref "BT1") (pin "1") (pinfunction "+_1") (pintype "power_in"))
      (node (ref "C8") (pin "1") (pinfunction "1_1") (pintype "passive"))
      (node (ref "DD1A") (pin "14") (pinfunction "VBAT_14") (pintype "bidirectional"))
      (node (ref "DD1B") (pin "3") (pinfunction "VBAT_3") (pintype "passive"))
    )
    (net (code "249") (name "unconnected-(DD2-ADC6-Pad19)") (class "Default")
      (node (ref "DD2") (pin "19") (pinfunction "ADC6_19") (pintype "bidirectional"))
    )
    (net (code "250") (name "unconnected-(DD2-ADC7-Pad22)") (class "Default")
      (node (ref "DD2") (pin "22") (pinfunction "ADC7_22") (pintype "bidirectional"))
    )
    (net (code "251") (name "unconnected-(DD2-AREF-Pad20)") (class "Default")
      (node (ref "DD2") (pin "20") (pinfunction "AREF_20") (pintype "passive"))
    )
    (net (code "252") (name "unconnected-(DD2-PB0(ICP)-Pad12)") (class "Default")
      (node (ref "DD2") (pin "12") (pinfunction "PB0(ICP)_12") (pintype "bidirectional"))
    )
    (net (code "253") (name "unconnected-(DD2-PB1(OC1A)-Pad13)") (class "Default")
      (node (ref "DD2") (pin "13") (pinfunction "PB1(OC1A)_13") (pintype "bidirectional"))
    )
    (net (code "254") (name "unconnected-(DD2-PC0(ADC0)-Pad23)") (class "Default")
      (node (ref "DD2") (pin "23") (pinfunction "PC0(ADC0)_23") (pintype "bidirectional"))
    )
    (net (code "255") (name "unconnected-(DD2-PC1(ADC1)-Pad24)") (class "Default")
      (node (ref "DD2") (pin "24") (pinfunction "PC1(ADC1)_24") (pintype "bidirectional"))
    )
    (net (code "256") (name "unconnected-(DD2-PC2(ADC2)-Pad25)") (class "Default")
      (node (ref "DD2") (pin "25") (pinfunction "PC2(ADC2)_25") (pintype "bidirectional"))
    )
    (net (code "257") (name "unconnected-(DD2-PC3(ADC3)-Pad26)") (class "Default")
      (node (ref "DD2") (pin "26") (pinfunction "PC3(ADC3)_26") (pintype "bidirectional"))
    )
    (net (code "258") (name "unconnected-(DD2-PD0(RXD)-Pad30)") (class "Default")
      (node (ref "DD2") (pin "30") (pinfunction "PD0(RXD)_30") (pintype "bidirectional"))
    )
    (net (code "259") (name "unconnected-(DD2-PD1(TXD)-Pad31)") (class "Default")
      (node (ref "DD2") (pin "31") (pinfunction "PD1(TXD)_31") (pintype "bidirectional"))
    )
    (net (code "260") (name "unconnected-(DD2-PD3(INT1)-Pad1)") (class "Default")
      (node (ref "DD2") (pin "1") (pinfunction "PD3(INT1)_1") (pintype "bidirectional"))
    )
    (net (code "261") (name "unconnected-(DD2-PD4(XCK{slash}T0)-Pad2)") (class "Default")
      (node (ref "DD2") (pin "2") (pinfunction "PD4(XCK/T0)_2") (pintype "bidirectional"))
    )
    (net (code "262") (name "unconnected-(DD2-PD5(T1)-Pad9)") (class "Default")
      (node (ref "DD2") (pin "9") (pinfunction "PD5(T1)_9") (pintype "bidirectional"))
    )
    (net (code "263") (name "unconnected-(DD2-PD6(AIN0)-Pad10)") (class "Default")
      (node (ref "DD2") (pin "10") (pinfunction "PD6(AIN0)_10") (pintype "bidirectional"))
    )
    (net (code "264") (name "unconnected-(DD2-PD7(AIN1)-Pad11)") (class "Default")
      (node (ref "DD2") (pin "11") (pinfunction "PD7(AIN1)_11") (pintype "bidirectional"))
    )
    (net (code "265") (name "unconnected-(IC7A-QE-Pad4)") (class "Default")
      (node (ref "IC7") (pin "4") (pinfunction "QE_4") (pintype "tri_state"))
    )
    (net (code "266") (name "unconnected-(IC7A-QF-Pad5)") (class "Default")
      (node (ref "IC7") (pin "5") (pinfunction "QF_5") (pintype "tri_state"))
    )
    (net (code "267") (name "unconnected-(IC7A-QG-Pad6)") (class "Default")
      (node (ref "IC7") (pin "6") (pinfunction "QG_6") (pintype "tri_state"))
    )
    (net (code "268") (name "unconnected-(IC7A-QH*-Pad9)") (class "Default")
      (node (ref "IC7") (pin "9") (pinfunction "QH*_9") (pintype "tri_state"))
    )
    (net (code "269") (name "unconnected-(IC7A-QH-Pad7)") (class "Default")
      (node (ref "IC7") (pin "7") (pinfunction "QH_7") (pintype "tri_state"))
    )
  )
)
